# PP-Rev2.net
KiCad netlist of a schematic drawn in EAGLE
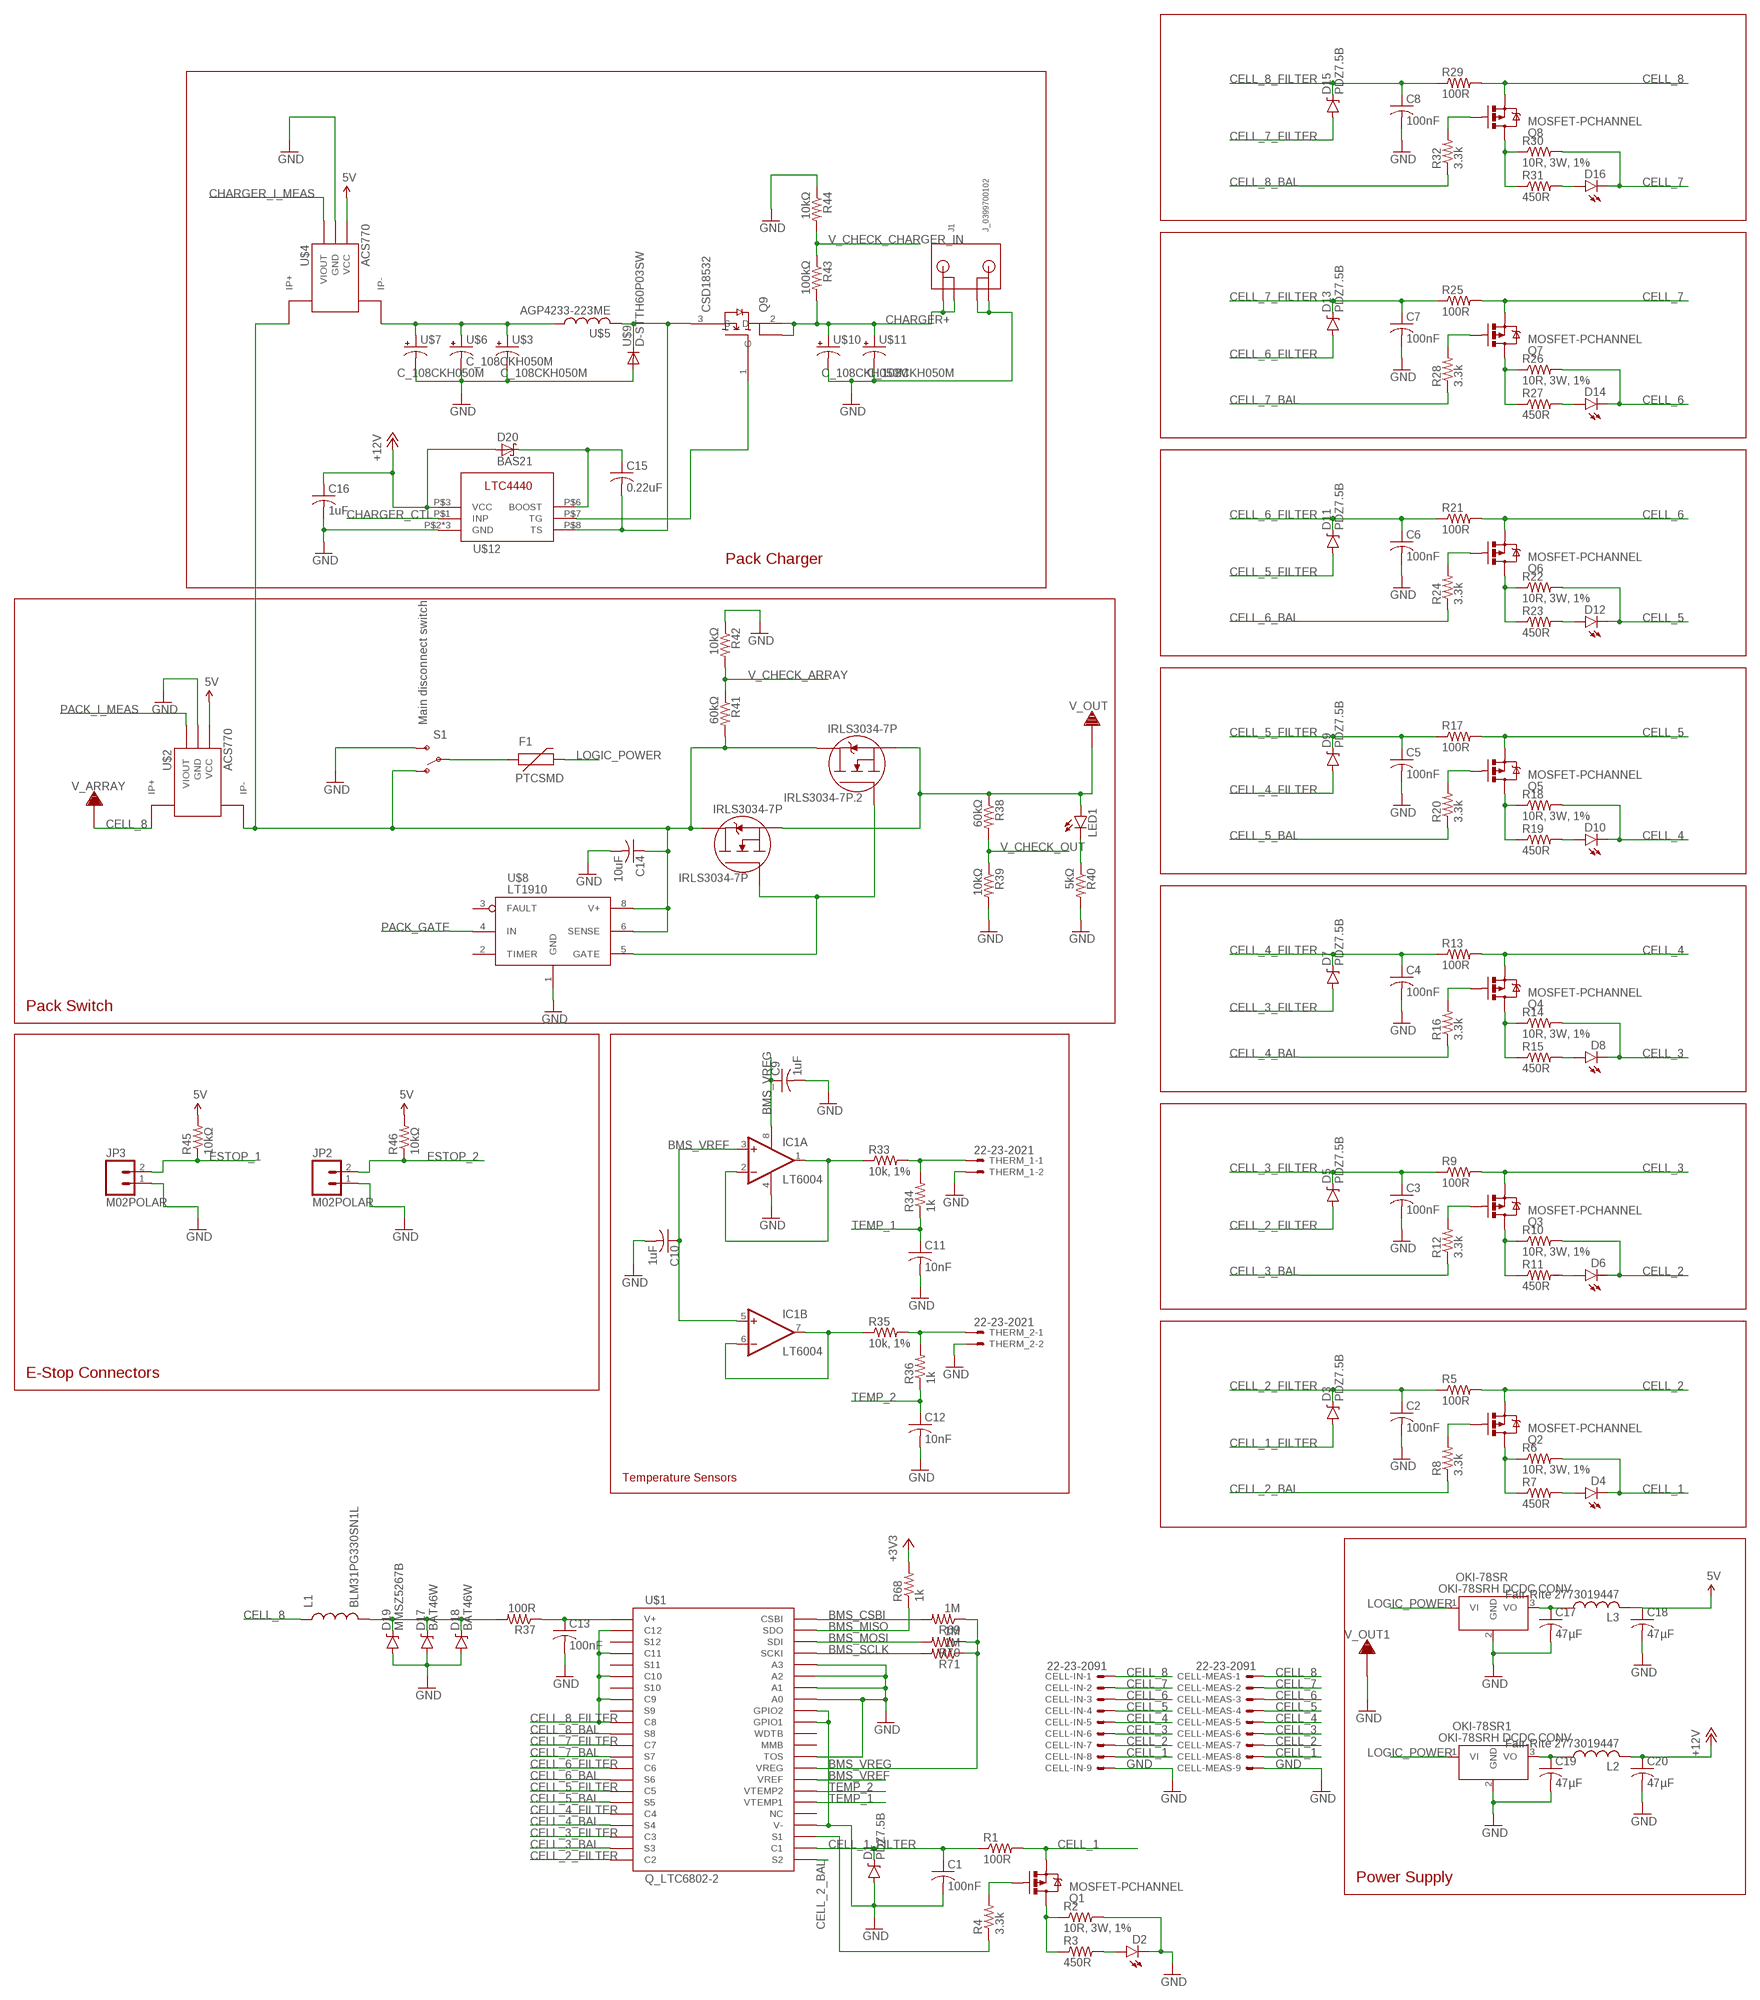
[diagram p0: schematic, sheet 1, part 1 of 2]
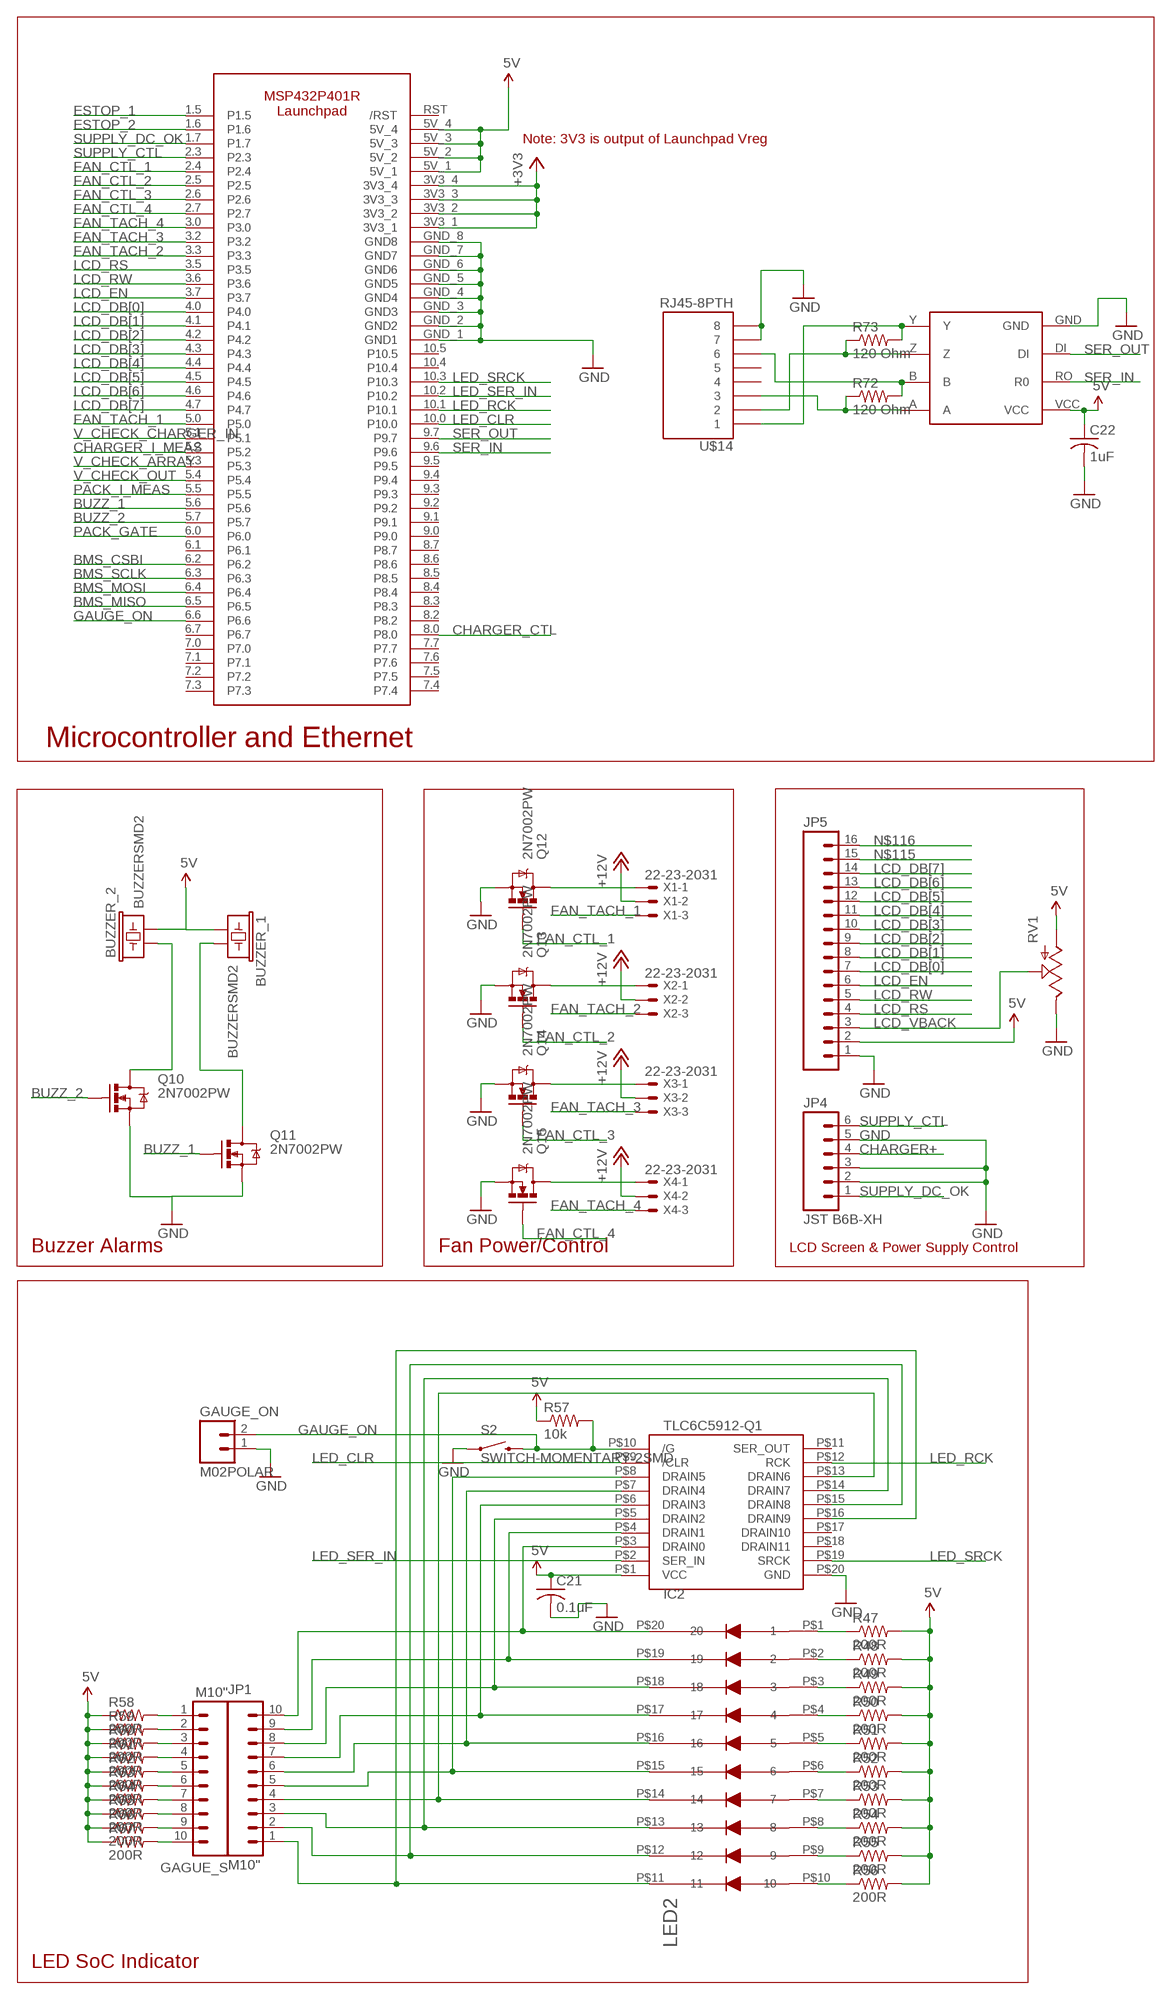
[diagram p1: schematic, sheet 1, part 2 of 2]

(export (version "E")
  (design (tool "Eeschema 10.0.6"))
  (components
    (comp (ref "BUZZER_1")
      (value "BUZZERSMD2")
      (footprint "eagle-import:BUZZER-CCV")
      (libsource (lib "eagle-import") (part "BUZZERSMD2"))
    )
    (comp (ref "BUZZER_2")
      (value "BUZZERSMD2")
      (footprint "eagle-import:BUZZER-CCV")
      (libsource (lib "eagle-import") (part "BUZZERSMD2"))
    )
    (comp (ref "C1")
      (value "100nF")
      (footprint "eagle-import:C1206")
      (libsource (lib "eagle-import") (part "C-USC1206"))
    )
    (comp (ref "C2")
      (value "100nF")
      (footprint "eagle-import:C1206")
      (libsource (lib "eagle-import") (part "C-USC1206"))
    )
    (comp (ref "C3")
      (value "100nF")
      (footprint "eagle-import:C1206")
      (libsource (lib "eagle-import") (part "C-USC1206"))
    )
    (comp (ref "C4")
      (value "100nF")
      (footprint "eagle-import:C1206")
      (libsource (lib "eagle-import") (part "C-USC1206"))
    )
    (comp (ref "C5")
      (value "100nF")
      (footprint "eagle-import:C1206")
      (libsource (lib "eagle-import") (part "C-USC1206"))
    )
    (comp (ref "C6")
      (value "100nF")
      (footprint "eagle-import:C1206")
      (libsource (lib "eagle-import") (part "C-USC1206"))
    )
    (comp (ref "C7")
      (value "100nF")
      (footprint "eagle-import:C1206")
      (libsource (lib "eagle-import") (part "C-USC1206"))
    )
    (comp (ref "C8")
      (value "100nF")
      (footprint "eagle-import:C1206")
      (libsource (lib "eagle-import") (part "C-USC1206"))
    )
    (comp (ref "C9")
      (value "1uF")
      (footprint "eagle-import:C1206")
      (libsource (lib "eagle-import") (part "C-USC1206"))
    )
    (comp (ref "C10")
      (value "1uF")
      (footprint "eagle-import:C1206")
      (libsource (lib "eagle-import") (part "C-USC1206"))
    )
    (comp (ref "C11")
      (value "10nF")
      (footprint "eagle-import:C1206")
      (libsource (lib "eagle-import") (part "C-USC1206"))
    )
    (comp (ref "C12")
      (value "10nF")
      (footprint "eagle-import:C1206")
      (libsource (lib "eagle-import") (part "C-USC1206"))
    )
    (comp (ref "C13")
      (value "100nF")
      (footprint "eagle-import:C1206")
      (libsource (lib "eagle-import") (part "C-USC1206"))
    )
    (comp (ref "C14")
      (value "10uF")
      (footprint "eagle-import:C1206")
      (libsource (lib "eagle-import") (part "C-USC1206"))
    )
    (comp (ref "C15")
      (value "0.22uF")
      (footprint "eagle-import:C1206")
      (libsource (lib "eagle-import") (part "C-USC1206"))
    )
    (comp (ref "C16")
      (value "1uF")
      (footprint "eagle-import:C1206")
      (libsource (lib "eagle-import") (part "C-USC1206"))
    )
    (comp (ref "C17")
      (value "47µF")
      (footprint "eagle-import:C1206")
      (libsource (lib "eagle-import") (part "resistor_C-USC1206"))
    )
    (comp (ref "C18")
      (value "47µF")
      (footprint "eagle-import:C1206")
      (libsource (lib "eagle-import") (part "resistor_C-USC1206"))
    )
    (comp (ref "C19")
      (value "47µF")
      (footprint "eagle-import:C1206")
      (libsource (lib "eagle-import") (part "resistor_C-USC1206"))
    )
    (comp (ref "C20")
      (value "47µF")
      (footprint "eagle-import:C1206")
      (libsource (lib "eagle-import") (part "resistor_C-USC1206"))
    )
    (comp (ref "C21")
      (value "0.1uF")
      (footprint "eagle-import:C1206")
      (libsource (lib "eagle-import") (part "resistor_C-USC1206"))
    )
    (comp (ref "C22")
      (value "1uF")
      (footprint "eagle-import:C1206")
      (libsource (lib "eagle-import") (part "resistor_C-USC1206"))
    )
    (comp (ref "CELL-IN")
      (value "22-23-2091")
      (footprint "eagle-import:22-23-2091")
      (fields (field (name "MF") "MOLEX"))
      (libsource (lib "eagle-import") (part "22-23-2091"))
    )
    (comp (ref "CELL-MEAS")
      (value "22-23-2091")
      (footprint "eagle-import:22-23-2091")
      (fields (field (name "MF") "MOLEX"))
      (libsource (lib "eagle-import") (part "22-23-2091"))
    )
    (comp (ref "D1")
      (value "PDZ7.5B")
      (footprint "eagle-import:SOD-323")
      (libsource (lib "eagle-import") (part "DIODE-ZENER5.6V"))
    )
    (comp (ref "D2")
      (value "LED1206")
      (footprint "eagle-import:LED-1206")
      (libsource (lib "eagle-import") (part "LED1206"))
    )
    (comp (ref "D3")
      (value "PDZ7.5B")
      (footprint "eagle-import:SOD-323")
      (libsource (lib "eagle-import") (part "DIODE-ZENER5.6V"))
    )
    (comp (ref "D4")
      (value "LED1206")
      (footprint "eagle-import:LED-1206")
      (libsource (lib "eagle-import") (part "LED1206"))
    )
    (comp (ref "D5")
      (value "PDZ7.5B")
      (footprint "eagle-import:SOD-323")
      (libsource (lib "eagle-import") (part "DIODE-ZENER5.6V"))
    )
    (comp (ref "D6")
      (value "LED1206")
      (footprint "eagle-import:LED-1206")
      (libsource (lib "eagle-import") (part "LED1206"))
    )
    (comp (ref "D7")
      (value "PDZ7.5B")
      (footprint "eagle-import:SOD-323")
      (libsource (lib "eagle-import") (part "DIODE-ZENER5.6V"))
    )
    (comp (ref "D8")
      (value "LED1206")
      (footprint "eagle-import:LED-1206")
      (libsource (lib "eagle-import") (part "LED1206"))
    )
    (comp (ref "D9")
      (value "PDZ7.5B")
      (footprint "eagle-import:SOD-323")
      (libsource (lib "eagle-import") (part "DIODE-ZENER5.6V"))
    )
    (comp (ref "D10")
      (value "LED1206")
      (footprint "eagle-import:LED-1206")
      (libsource (lib "eagle-import") (part "LED1206"))
    )
    (comp (ref "D11")
      (value "PDZ7.5B")
      (footprint "eagle-import:SOD-323")
      (libsource (lib "eagle-import") (part "DIODE-ZENER5.6V"))
    )
    (comp (ref "D12")
      (value "LED1206")
      (footprint "eagle-import:LED-1206")
      (libsource (lib "eagle-import") (part "LED1206"))
    )
    (comp (ref "D13")
      (value "PDZ7.5B")
      (footprint "eagle-import:SOD-323")
      (libsource (lib "eagle-import") (part "DIODE-ZENER5.6V"))
    )
    (comp (ref "D14")
      (value "LED1206")
      (footprint "eagle-import:LED-1206")
      (libsource (lib "eagle-import") (part "LED1206"))
    )
    (comp (ref "D15")
      (value "PDZ7.5B")
      (footprint "eagle-import:SOD-323")
      (libsource (lib "eagle-import") (part "DIODE-ZENER5.6V"))
    )
    (comp (ref "D16")
      (value "LED1206")
      (footprint "eagle-import:LED-1206")
      (libsource (lib "eagle-import") (part "LED1206"))
    )
    (comp (ref "D17")
      (value "BAT46W")
      (footprint "eagle-import:SOD-123")
      (libsource (lib "eagle-import") (part "DIODE-ZENER16V"))
    )
    (comp (ref "D18")
      (value "BAT46W")
      (footprint "eagle-import:SOD-123")
      (libsource (lib "eagle-import") (part "DIODE-ZENER16V"))
    )
    (comp (ref "D19")
      (value "MMSZ5267B")
      (footprint "eagle-import:SOD-123")
      (libsource (lib "eagle-import") (part "DIODE-ZENER16V"))
    )
    (comp (ref "D20")
      (value "BAS21")
      (footprint "eagle-import:SOT23")
      (libsource (lib "eagle-import") (part "BAS40"))
    )
    (comp (ref "F1")
      (value "PTCSMD")
      (footprint "eagle-import:PTC-1206")
      (libsource (lib "eagle-import") (part "PTCSMD"))
    )
    (comp (ref "GAGUE_S")
      (value "M10\"")
      (footprint "eagle-import:1X10")
      (libsource (lib "eagle-import") (part "M10{dblquote}"))
    )
    (comp (ref "GAUGE_ON")
      (value "M02POLAR")
      (footprint "eagle-import:MOLEX-1X2")
      (libsource (lib "eagle-import") (part "M02POLAR"))
    )
    (comp (ref "IC1")
      (value "LT6004")
      (footprint "eagle-import:MSOP08")
      (libsource (lib "eagle-import") (part "OPA2E345"))
    )
    (comp (ref "IC2")
      (value "TLC6C5912-Q1")
      (footprint "eagle-import:SOIC-20")
      (libsource (lib "eagle-import") (part "TLC6C5912-Q1"))
    )
    (comp (ref "IRLS3034-7P")
      (value "IRLS3034-7P")
      (footprint "eagle-import:D2PAK-7")
      (libsource (lib "eagle-import") (part "IRLS3034-7P"))
    )
    (comp (ref "IRLS3034-7P.2")
      (value "IRLS3034-7P")
      (footprint "eagle-import:D2PAK-7")
      (libsource (lib "eagle-import") (part "IRLS3034-7P"))
    )
    (comp (ref "J1")
      (value "J_0399700102")
      (footprint "eagle-import:J_2CONHC")
      (libsource (lib "eagle-import") (part "J_0399700102"))
    )
    (comp (ref "JP1")
      (value "M10\"")
      (footprint "eagle-import:1X10")
      (libsource (lib "eagle-import") (part "M10{dblquote}"))
    )
    (comp (ref "JP2")
      (value "M02POLAR")
      (footprint "eagle-import:MOLEX-1X2")
      (libsource (lib "eagle-import") (part "M02POLAR"))
    )
    (comp (ref "JP3")
      (value "M02POLAR")
      (footprint "eagle-import:MOLEX-1X2")
      (libsource (lib "eagle-import") (part "M02POLAR"))
    )
    (comp (ref "JP4")
      (value "JST B6B-XH")
      (footprint "eagle-import:MOLEX-1X6")
      (libsource (lib "eagle-import") (part "M06POLAR"))
    )
    (comp (ref "JP5")
      (value "M16LONGPADS")
      (footprint "eagle-import:1X16_LONGPADS")
      (libsource (lib "eagle-import") (part "M16LONGPADS"))
    )
    (comp (ref "L1")
      (value "BLM31PG330SN1L")
      (footprint "eagle-import:1210")
      (libsource (lib "eagle-import") (part "INDUCTOR1210"))
    )
    (comp (ref "L2")
      (value "Fair-Rite 2773019447")
      (footprint "eagle-import:L8530M")
      (libsource (lib "eagle-import") (part "L-USL8530M"))
    )
    (comp (ref "L3")
      (value "Fair-Rite 2773019447")
      (footprint "eagle-import:L8530M")
      (libsource (lib "eagle-import") (part "L-USL8530M"))
    )
    (comp (ref "LED1")
      (value "LED1206")
      (footprint "eagle-import:LED-1206")
      (libsource (lib "eagle-import") (part "LED1206"))
    )
    (comp (ref "LED2")
      (value "LED-DC7G3HWA")
      (footprint "eagle-import:LED-10")
      (libsource (lib "eagle-import") (part "LED-DC7G3HWA"))
    )
    (comp (ref "OKI-78SR")
      (value "Q_OKI-78SR5")
      (footprint "eagle-import:OKI-78SRH")
      (libsource (lib "eagle-import") (part "Q_OKI-78SR"))
    )
    (comp (ref "OKI-78SR1")
      (value "Q_OKI-78SR12")
      (footprint "eagle-import:OKI-78SRH")
      (libsource (lib "eagle-import") (part "Q_OKI-78SR"))
    )
    (comp (ref "Q1")
      (value "MOSFET-PCHANNEL")
      (footprint "eagle-import:SOT23-3")
      (libsource (lib "eagle-import") (part "MOSFET-PCHANNEL"))
    )
    (comp (ref "Q2")
      (value "MOSFET-PCHANNEL")
      (footprint "eagle-import:SOT23-3")
      (libsource (lib "eagle-import") (part "MOSFET-PCHANNEL"))
    )
    (comp (ref "Q3")
      (value "MOSFET-PCHANNEL")
      (footprint "eagle-import:SOT23-3")
      (libsource (lib "eagle-import") (part "MOSFET-PCHANNEL"))
    )
    (comp (ref "Q4")
      (value "MOSFET-PCHANNEL")
      (footprint "eagle-import:SOT23-3")
      (libsource (lib "eagle-import") (part "MOSFET-PCHANNEL"))
    )
    (comp (ref "Q5")
      (value "MOSFET-PCHANNEL")
      (footprint "eagle-import:SOT23-3")
      (libsource (lib "eagle-import") (part "MOSFET-PCHANNEL"))
    )
    (comp (ref "Q6")
      (value "MOSFET-PCHANNEL")
      (footprint "eagle-import:SOT23-3")
      (libsource (lib "eagle-import") (part "MOSFET-PCHANNEL"))
    )
    (comp (ref "Q7")
      (value "MOSFET-PCHANNEL")
      (footprint "eagle-import:SOT23-3")
      (libsource (lib "eagle-import") (part "MOSFET-PCHANNEL"))
    )
    (comp (ref "Q8")
      (value "MOSFET-PCHANNEL")
      (footprint "eagle-import:SOT23-3")
      (libsource (lib "eagle-import") (part "MOSFET-PCHANNEL"))
    )
    (comp (ref "Q9")
      (value "CSD18532")
      (footprint "eagle-import:TO-220-FLAT")
      (libsource (lib "eagle-import") (part "Q_CSD18532KCSPCB"))
    )
    (comp (ref "Q10")
      (value "2N7002PW")
      (footprint "eagle-import:SOT323")
      (libsource (lib "eagle-import") (part "MOSFET-NCHANNEL2N7002PW"))
    )
    (comp (ref "Q11")
      (value "2N7002PW")
      (footprint "eagle-import:SOT323")
      (libsource (lib "eagle-import") (part "MOSFET-NCHANNEL2N7002PW"))
    )
    (comp (ref "Q12")
      (value "2N7002PW")
      (footprint "eagle-import:SOT323")
      (libsource (lib "eagle-import") (part "MOSFET-NCHANNEL2N7002PW"))
    )
    (comp (ref "Q13")
      (value "2N7002PW")
      (footprint "eagle-import:SOT323")
      (libsource (lib "eagle-import") (part "MOSFET-NCHANNEL2N7002PW"))
    )
    (comp (ref "Q14")
      (value "2N7002PW")
      (footprint "eagle-import:SOT323")
      (libsource (lib "eagle-import") (part "MOSFET-NCHANNEL2N7002PW"))
    )
    (comp (ref "Q15")
      (value "2N7002PW")
      (footprint "eagle-import:SOT323")
      (libsource (lib "eagle-import") (part "MOSFET-NCHANNEL2N7002PW"))
    )
    (comp (ref "R1")
      (value "100R")
      (footprint "eagle-import:R1206")
      (libsource (lib "eagle-import") (part "R-US_R1206"))
    )
    (comp (ref "R2")
      (value "10R, 3W, 1%")
      (footprint "eagle-import:AXIAL-0.6")
      (libsource (lib "eagle-import") (part "SparkFun-Resistors_RESISTORPTH-1W"))
    )
    (comp (ref "R3")
      (value "450R")
      (footprint "eagle-import:1206")
      (libsource (lib "eagle-import") (part "SparkFun-Resistors_RESISTOR1206"))
    )
    (comp (ref "R4")
      (value "3.3k")
      (footprint "eagle-import:1206")
      (libsource (lib "eagle-import") (part "SparkFun-Resistors_RESISTOR1206"))
    )
    (comp (ref "R5")
      (value "100R")
      (footprint "eagle-import:R1206")
      (libsource (lib "eagle-import") (part "R-US_R1206"))
    )
    (comp (ref "R6")
      (value "10R, 3W, 1%")
      (footprint "eagle-import:AXIAL-0.6")
      (libsource (lib "eagle-import") (part "SparkFun-Resistors_RESISTORPTH-1W"))
    )
    (comp (ref "R7")
      (value "450R")
      (footprint "eagle-import:1206")
      (libsource (lib "eagle-import") (part "SparkFun-Resistors_RESISTOR1206"))
    )
    (comp (ref "R8")
      (value "3.3k")
      (footprint "eagle-import:1206")
      (libsource (lib "eagle-import") (part "SparkFun-Resistors_RESISTOR1206"))
    )
    (comp (ref "R9")
      (value "100R")
      (footprint "eagle-import:R1206")
      (libsource (lib "eagle-import") (part "R-US_R1206"))
    )
    (comp (ref "R10")
      (value "10R, 3W, 1%")
      (footprint "eagle-import:AXIAL-0.6")
      (libsource (lib "eagle-import") (part "SparkFun-Resistors_RESISTORPTH-1W"))
    )
    (comp (ref "R11")
      (value "450R")
      (footprint "eagle-import:1206")
      (libsource (lib "eagle-import") (part "SparkFun-Resistors_RESISTOR1206"))
    )
    (comp (ref "R12")
      (value "3.3k")
      (footprint "eagle-import:1206")
      (libsource (lib "eagle-import") (part "SparkFun-Resistors_RESISTOR1206"))
    )
    (comp (ref "R13")
      (value "100R")
      (footprint "eagle-import:R1206")
      (libsource (lib "eagle-import") (part "R-US_R1206"))
    )
    (comp (ref "R14")
      (value "10R, 3W, 1%")
      (footprint "eagle-import:AXIAL-0.6")
      (libsource (lib "eagle-import") (part "SparkFun-Resistors_RESISTORPTH-1W"))
    )
    (comp (ref "R15")
      (value "450R")
      (footprint "eagle-import:1206")
      (libsource (lib "eagle-import") (part "SparkFun-Resistors_RESISTOR1206"))
    )
    (comp (ref "R16")
      (value "3.3k")
      (footprint "eagle-import:1206")
      (libsource (lib "eagle-import") (part "SparkFun-Resistors_RESISTOR1206"))
    )
    (comp (ref "R17")
      (value "100R")
      (footprint "eagle-import:R1206")
      (libsource (lib "eagle-import") (part "R-US_R1206"))
    )
    (comp (ref "R18")
      (value "10R, 3W, 1%")
      (footprint "eagle-import:AXIAL-0.6")
      (libsource (lib "eagle-import") (part "SparkFun-Resistors_RESISTORPTH-1W"))
    )
    (comp (ref "R19")
      (value "450R")
      (footprint "eagle-import:1206")
      (libsource (lib "eagle-import") (part "SparkFun-Resistors_RESISTOR1206"))
    )
    (comp (ref "R20")
      (value "3.3k")
      (footprint "eagle-import:1206")
      (libsource (lib "eagle-import") (part "SparkFun-Resistors_RESISTOR1206"))
    )
    (comp (ref "R21")
      (value "100R")
      (footprint "eagle-import:R1206")
      (libsource (lib "eagle-import") (part "R-US_R1206"))
    )
    (comp (ref "R22")
      (value "10R, 3W, 1%")
      (footprint "eagle-import:AXIAL-0.6")
      (libsource (lib "eagle-import") (part "SparkFun-Resistors_RESISTORPTH-1W"))
    )
    (comp (ref "R23")
      (value "450R")
      (footprint "eagle-import:1206")
      (libsource (lib "eagle-import") (part "SparkFun-Resistors_RESISTOR1206"))
    )
    (comp (ref "R24")
      (value "3.3k")
      (footprint "eagle-import:1206")
      (libsource (lib "eagle-import") (part "SparkFun-Resistors_RESISTOR1206"))
    )
    (comp (ref "R25")
      (value "100R")
      (footprint "eagle-import:R1206")
      (libsource (lib "eagle-import") (part "R-US_R1206"))
    )
    (comp (ref "R26")
      (value "10R, 3W, 1%")
      (footprint "eagle-import:AXIAL-0.6")
      (libsource (lib "eagle-import") (part "SparkFun-Resistors_RESISTORPTH-1W"))
    )
    (comp (ref "R27")
      (value "450R")
      (footprint "eagle-import:1206")
      (libsource (lib "eagle-import") (part "SparkFun-Resistors_RESISTOR1206"))
    )
    (comp (ref "R28")
      (value "3.3k")
      (footprint "eagle-import:1206")
      (libsource (lib "eagle-import") (part "SparkFun-Resistors_RESISTOR1206"))
    )
    (comp (ref "R29")
      (value "100R")
      (footprint "eagle-import:R1206")
      (libsource (lib "eagle-import") (part "R-US_R1206"))
    )
    (comp (ref "R30")
      (value "10R, 3W, 1%")
      (footprint "eagle-import:AXIAL-0.6")
      (libsource (lib "eagle-import") (part "SparkFun-Resistors_RESISTORPTH-1W"))
    )
    (comp (ref "R31")
      (value "450R")
      (footprint "eagle-import:1206")
      (libsource (lib "eagle-import") (part "SparkFun-Resistors_RESISTOR1206"))
    )
    (comp (ref "R32")
      (value "3.3k")
      (footprint "eagle-import:1206")
      (libsource (lib "eagle-import") (part "SparkFun-Resistors_RESISTOR1206"))
    )
    (comp (ref "R33")
      (value "10k, 1%")
      (footprint "eagle-import:R1206")
      (libsource (lib "eagle-import") (part "R-US_R1206"))
    )
    (comp (ref "R34")
      (value "1k")
      (footprint "eagle-import:R1206")
      (libsource (lib "eagle-import") (part "R-US_R1206"))
    )
    (comp (ref "R35")
      (value "10k, 1%")
      (footprint "eagle-import:R1206")
      (libsource (lib "eagle-import") (part "R-US_R1206"))
    )
    (comp (ref "R36")
      (value "1k")
      (footprint "eagle-import:R1206")
      (libsource (lib "eagle-import") (part "R-US_R1206"))
    )
    (comp (ref "R37")
      (value "100R")
      (footprint "eagle-import:R1206")
      (libsource (lib "eagle-import") (part "R-US_R1206"))
    )
    (comp (ref "R38")
      (value "60kΩ")
      (footprint "eagle-import:R1206")
      (libsource (lib "eagle-import") (part "resistor_R-US_R1206"))
    )
    (comp (ref "R39")
      (value "10kΩ")
      (footprint "eagle-import:R1206")
      (libsource (lib "eagle-import") (part "resistor_R-US_R1206"))
    )
    (comp (ref "R40")
      (value "5kΩ")
      (footprint "eagle-import:R1206")
      (libsource (lib "eagle-import") (part "resistor_R-US_R1206"))
    )
    (comp (ref "R41")
      (value "60kΩ")
      (footprint "eagle-import:R1206")
      (libsource (lib "eagle-import") (part "resistor_R-US_R1206"))
    )
    (comp (ref "R42")
      (value "10kΩ")
      (footprint "eagle-import:R1206")
      (libsource (lib "eagle-import") (part "resistor_R-US_R1206"))
    )
    (comp (ref "R43")
      (value "100kΩ")
      (footprint "eagle-import:R1206")
      (libsource (lib "eagle-import") (part "resistor_R-US_R1206"))
    )
    (comp (ref "R44")
      (value "10kΩ")
      (footprint "eagle-import:R1206")
      (libsource (lib "eagle-import") (part "resistor_R-US_R1206"))
    )
    (comp (ref "R45")
      (value "10kΩ")
      (footprint "eagle-import:R1206")
      (libsource (lib "eagle-import") (part "resistor_R-US_R1206"))
    )
    (comp (ref "R46")
      (value "10kΩ")
      (footprint "eagle-import:R1206")
      (libsource (lib "eagle-import") (part "resistor_R-US_R1206"))
    )
    (comp (ref "R47")
      (value "200R")
      (footprint "eagle-import:R1206")
      (libsource (lib "eagle-import") (part "R-US_R1206"))
    )
    (comp (ref "R48")
      (value "200R")
      (footprint "eagle-import:R1206")
      (libsource (lib "eagle-import") (part "R-US_R1206"))
    )
    (comp (ref "R49")
      (value "200R")
      (footprint "eagle-import:R1206")
      (libsource (lib "eagle-import") (part "R-US_R1206"))
    )
    (comp (ref "R50")
      (value "200R")
      (footprint "eagle-import:R1206")
      (libsource (lib "eagle-import") (part "R-US_R1206"))
    )
    (comp (ref "R51")
      (value "200R")
      (footprint "eagle-import:R1206")
      (libsource (lib "eagle-import") (part "R-US_R1206"))
    )
    (comp (ref "R52")
      (value "200R")
      (footprint "eagle-import:R1206")
      (libsource (lib "eagle-import") (part "R-US_R1206"))
    )
    (comp (ref "R53")
      (value "200R")
      (footprint "eagle-import:R1206")
      (libsource (lib "eagle-import") (part "R-US_R1206"))
    )
    (comp (ref "R54")
      (value "200R")
      (footprint "eagle-import:R1206")
      (libsource (lib "eagle-import") (part "R-US_R1206"))
    )
    (comp (ref "R55")
      (value "200R")
      (footprint "eagle-import:R1206")
      (libsource (lib "eagle-import") (part "R-US_R1206"))
    )
    (comp (ref "R56")
      (value "200R")
      (footprint "eagle-import:R1206")
      (libsource (lib "eagle-import") (part "R-US_R1206"))
    )
    (comp (ref "R57")
      (value "10k")
      (footprint "eagle-import:R1206")
      (libsource (lib "eagle-import") (part "R-US_R1206"))
    )
    (comp (ref "R58")
      (value "200R")
      (footprint "eagle-import:R1206")
      (libsource (lib "eagle-import") (part "R-US_R1206"))
    )
    (comp (ref "R59")
      (value "200R")
      (footprint "eagle-import:R1206")
      (libsource (lib "eagle-import") (part "R-US_R1206"))
    )
    (comp (ref "R60")
      (value "200R")
      (footprint "eagle-import:R1206")
      (libsource (lib "eagle-import") (part "R-US_R1206"))
    )
    (comp (ref "R61")
      (value "200R")
      (footprint "eagle-import:R1206")
      (libsource (lib "eagle-import") (part "R-US_R1206"))
    )
    (comp (ref "R62")
      (value "200R")
      (footprint "eagle-import:R1206")
      (libsource (lib "eagle-import") (part "R-US_R1206"))
    )
    (comp (ref "R63")
      (value "200R")
      (footprint "eagle-import:R1206")
      (libsource (lib "eagle-import") (part "R-US_R1206"))
    )
    (comp (ref "R64")
      (value "200R")
      (footprint "eagle-import:R1206")
      (libsource (lib "eagle-import") (part "R-US_R1206"))
    )
    (comp (ref "R65")
      (value "200R")
      (footprint "eagle-import:R1206")
      (libsource (lib "eagle-import") (part "R-US_R1206"))
    )
    (comp (ref "R66")
      (value "200R")
      (footprint "eagle-import:R1206")
      (libsource (lib "eagle-import") (part "R-US_R1206"))
    )
    (comp (ref "R67")
      (value "200R")
      (footprint "eagle-import:R1206")
      (libsource (lib "eagle-import") (part "R-US_R1206"))
    )
    (comp (ref "R68")
      (value "1k")
      (footprint "eagle-import:R1206")
      (libsource (lib "eagle-import") (part "R-US_R1206"))
    )
    (comp (ref "R69")
      (value "1M")
      (footprint "eagle-import:R1206")
      (libsource (lib "eagle-import") (part "R-US_R1206"))
    )
    (comp (ref "R70")
      (value "1M")
      (footprint "eagle-import:R1206")
      (libsource (lib "eagle-import") (part "R-US_R1206"))
    )
    (comp (ref "R71")
      (value "1M")
      (footprint "eagle-import:R1206")
      (libsource (lib "eagle-import") (part "R-US_R1206"))
    )
    (comp (ref "R72")
      (value "120 Ohm")
      (footprint "eagle-import:1206")
      (libsource (lib "eagle-import") (part "RESISTOR1206"))
    )
    (comp (ref "R73")
      (value "120 Ohm")
      (footprint "eagle-import:1206")
      (libsource (lib "eagle-import") (part "RESISTOR1206"))
    )
    (comp (ref "RV1")
      (value "POTTRIM")
      (footprint "eagle-import:TRIM_POT")
      (libsource (lib "eagle-import") (part "POTTRIM"))
    )
    (comp (ref "S1")
      (value "SWITCH-SPDTPTH")
      (footprint "eagle-import:SWITCH-SPDT")
      (libsource (lib "eagle-import") (part "SWITCH-SPDTPTH"))
    )
    (comp (ref "S2")
      (value "SWITCH-MOMENTARY-2SMD")
      (footprint "eagle-import:TACTILE-SWITCH-SMD")
      (libsource (lib "eagle-import") (part "SWITCH-MOMENTARY-2SMD"))
    )
    (comp (ref "THERM_1")
      (value "22-23-2021")
      (footprint "eagle-import:22-23-2021")
      (fields (field (name "MF") "MOLEX"))
      (libsource (lib "eagle-import") (part "22-23-2021"))
    )
    (comp (ref "THERM_2")
      (value "22-23-2021")
      (footprint "eagle-import:22-23-2021")
      (fields (field (name "MF") "MOLEX"))
      (libsource (lib "eagle-import") (part "22-23-2021"))
    )
    (comp (ref "U$1")
      (value "Q_LTC6802-2")
      (footprint "eagle-import:SSOP44")
      (libsource (lib "eagle-import") (part "Q_LTC6802-2"))
    )
    (comp (ref "U$2")
      (value "ACS770")
      (footprint "eagle-import:PFF_LEADFORM")
      (libsource (lib "eagle-import") (part "ACS770"))
    )
    (comp (ref "U$3")
      (value "C_108CKH050M")
      (footprint "eagle-import:C_16MM")
      (libsource (lib "eagle-import") (part "C_108CKH050M"))
    )
    (comp (ref "U$4")
      (value "ACS770")
      (footprint "eagle-import:PFF_LEADFORM")
      (libsource (lib "eagle-import") (part "ACS770"))
    )
    (comp (ref "U$5")
      (value "AGP4233-223ME")
      (footprint "eagle-import:AGP4233")
      (libsource (lib "eagle-import") (part "AGP4233"))
    )
    (comp (ref "U$6")
      (value "C_108CKH050M")
      (footprint "eagle-import:C_16MM")
      (libsource (lib "eagle-import") (part "C_108CKH050M"))
    )
    (comp (ref "U$7")
      (value "C_108CKH050M")
      (footprint "eagle-import:C_16MM")
      (libsource (lib "eagle-import") (part "C_108CKH050M"))
    )
    (comp (ref "U$8")
      (value "LT1910")
      (footprint "eagle-import:SO8")
      (libsource (lib "eagle-import") (part "LT1910"))
    )
    (comp (ref "U$9")
      (value "D-STTH60P03SW")
      (footprint "eagle-import:TO-247-VERT")
      (libsource (lib "eagle-import") (part "D-STTH60P03SW"))
    )
    (comp (ref "U$10")
      (value "C_108CKH050M")
      (footprint "eagle-import:C_16MM")
      (libsource (lib "eagle-import") (part "C_108CKH050M"))
    )
    (comp (ref "U$11")
      (value "C_108CKH050M")
      (footprint "eagle-import:C_16MM")
      (libsource (lib "eagle-import") (part "C_108CKH050M"))
    )
    (comp (ref "U$12")
      (value "LTC4440")
      (footprint "eagle-import:MS8E")
      (libsource (lib "eagle-import") (part "LTC4440"))
    )
    (comp (ref "U$13")
      (value "MSP432P401R-LAUNCHPAD")
      (footprint "eagle-import:MSP432P401R-LAUNCHPAD")
      (libsource (lib "eagle-import") (part "MSP432P401R-LAUNCHPAD"))
    )
    (comp (ref "U$14")
      (value "RJ45-8PTH")
      (footprint "eagle-import:RJ45-8")
      (libsource (lib "eagle-import") (part "RJ45-8PTH"))
    )
    (comp (ref "U$15")
      (value "MAX3077")
      (footprint "eagle-import:MAX3070E")
      (libsource (lib "eagle-import") (part "MAX3077"))
    )
    (comp (ref "V_ARRAY")
      (value "TERMINAL_HOLE")
      (footprint "eagle-import:LARGE_TERMINAL_HOLE")
      (libsource (lib "eagle-import") (part "TERMINAL_HOLE"))
    )
    (comp (ref "V_OUT")
      (value "TERMINAL_HOLE")
      (footprint "eagle-import:LARGE_TERMINAL_HOLE")
      (libsource (lib "eagle-import") (part "TERMINAL_HOLE"))
    )
    (comp (ref "V_OUT1")
      (value "TERMINAL_HOLE")
      (footprint "eagle-import:LARGE_TERMINAL_HOLE")
      (libsource (lib "eagle-import") (part "TERMINAL_HOLE"))
    )
    (comp (ref "X1")
      (value "22-23-2031")
      (footprint "eagle-import:22-23-2031")
      (fields (field (name "MF") "MOLEX"))
      (libsource (lib "eagle-import") (part "22-23-2031"))
    )
    (comp (ref "X2")
      (value "22-23-2031")
      (footprint "eagle-import:22-23-2031")
      (fields (field (name "MF") "MOLEX"))
      (libsource (lib "eagle-import") (part "22-23-2031"))
    )
    (comp (ref "X3")
      (value "22-23-2031")
      (footprint "eagle-import:22-23-2031")
      (fields (field (name "MF") "MOLEX"))
      (libsource (lib "eagle-import") (part "22-23-2031"))
    )
    (comp (ref "X4")
      (value "22-23-2031")
      (footprint "eagle-import:22-23-2031")
      (fields (field (name "MF") "MOLEX"))
      (libsource (lib "eagle-import") (part "22-23-2031"))
    )
  )
  (nets
    (net (code "1") (name "+3V3") (class "Default")
      (node (ref "R68") (pin "2") (pinfunction "2_2") (pintype "passive"))
      (node (ref "U$13") (pin "3V3_1") (pinfunction "3V3_1_3V3_1") (pintype "bidirectional"))
      (node (ref "U$13") (pin "3V3_2") (pinfunction "3V3_2_3V3_2") (pintype "bidirectional"))
      (node (ref "U$13") (pin "3V3_3") (pinfunction "3V3_3_3V3_3") (pintype "bidirectional"))
      (node (ref "U$13") (pin "3V3_4") (pinfunction "3V3_4_3V3_4") (pintype "bidirectional"))
    )
    (net (code "2") (name "+12V") (class "Default")
      (node (ref "C16") (pin "1") (pinfunction "1_1") (pintype "passive"))
      (node (ref "C20") (pin "1") (pinfunction "1_1") (pintype "passive"))
      (node (ref "D20") (pin "1") (pinfunction "A_1") (pintype "passive"))
      (node (ref "L2") (pin "2") (pinfunction "2_2") (pintype "passive"))
      (node (ref "U$12") (pin "P$3") (pinfunction "VCC_P$3") (pintype "bidirectional"))
      (node (ref "X1") (pin "2") (pinfunction "S_2") (pintype "passive"))
      (node (ref "X2") (pin "2") (pinfunction "S_2") (pintype "passive"))
      (node (ref "X3") (pin "2") (pinfunction "S_2") (pintype "passive"))
      (node (ref "X4") (pin "2") (pinfunction "S_2") (pintype "passive"))
    )
    (net (code "3") (name "/BMS_CSBI") (class "Default")
      (node (ref "R69") (pin "2") (pinfunction "2_2") (pintype "passive"))
      (node (ref "U$1") (pin "44") (pinfunction "CSBI_44") (pintype "bidirectional"))
      (node (ref "U$13") (pin "6.2") (pinfunction "P6.2_6.2") (pintype "bidirectional"))
    )
    (net (code "4") (name "/BMS_MISO") (class "Default")
      (node (ref "R68") (pin "1") (pinfunction "1_1") (pintype "passive"))
      (node (ref "U$1") (pin "43") (pinfunction "SDO_43") (pintype "bidirectional"))
      (node (ref "U$13") (pin "6.5") (pinfunction "P6.5_6.5") (pintype "bidirectional"))
    )
    (net (code "5") (name "/BMS_MOSI") (class "Default")
      (node (ref "R70") (pin "2") (pinfunction "2_2") (pintype "passive"))
      (node (ref "U$1") (pin "42") (pinfunction "SDI_42") (pintype "bidirectional"))
      (node (ref "U$13") (pin "6.4") (pinfunction "P6.4_6.4") (pintype "bidirectional"))
    )
    (net (code "6") (name "/BMS_SCLK") (class "Default")
      (node (ref "R71") (pin "2") (pinfunction "2_2") (pintype "passive"))
      (node (ref "U$1") (pin "41") (pinfunction "SCKI_41") (pintype "bidirectional"))
      (node (ref "U$13") (pin "6.3") (pinfunction "P6.3_6.3") (pintype "bidirectional"))
    )
    (net (code "7") (name "/BMS_VREF") (class "Default")
      (node (ref "C10") (pin "1") (pinfunction "1_1") (pintype "passive"))
      (node (ref "IC1") (pin "3") (pinfunction "+IN_3") (pintype "input"))
      (node (ref "IC1") (pin "5") (pinfunction "+IN_5") (pintype "input"))
      (node (ref "U$1") (pin "30") (pinfunction "VREF_30") (pintype "bidirectional"))
    )
    (net (code "8") (name "/BMS_VREG") (class "Default")
      (node (ref "C9") (pin "1") (pinfunction "1_1") (pintype "passive"))
      (node (ref "IC1") (pin "8") (pinfunction "V+_8") (pintype "power_in"))
      (node (ref "R69") (pin "1") (pinfunction "1_1") (pintype "passive"))
      (node (ref "R70") (pin "1") (pinfunction "1_1") (pintype "passive"))
      (node (ref "R71") (pin "1") (pinfunction "1_1") (pintype "passive"))
      (node (ref "U$1") (pin "31") (pinfunction "VREG_31") (pintype "bidirectional"))
    )
    (net (code "9") (name "/BUZZ_1") (class "Default")
      (node (ref "Q11") (pin "1") (pinfunction "G_1") (pintype "passive"))
      (node (ref "U$13") (pin "5.6") (pinfunction "P5.6_5.6") (pintype "bidirectional"))
    )
    (net (code "10") (name "/BUZZ_2") (class "Default")
      (node (ref "Q10") (pin "1") (pinfunction "G_1") (pintype "passive"))
      (node (ref "U$13") (pin "5.7") (pinfunction "P5.7_5.7") (pintype "bidirectional"))
    )
    (net (code "11") (name "/CELL_1") (class "Default")
      (node (ref "CELL-IN") (pin "8") (pinfunction "S_8") (pintype "passive"))
      (node (ref "CELL-MEAS") (pin "8") (pinfunction "S_8") (pintype "passive"))
      (node (ref "D4") (pin "C") (pinfunction "C_C") (pintype "passive"))
      (node (ref "Q1") (pin "2") (pinfunction "S_2") (pintype "passive"))
      (node (ref "R1") (pin "2") (pinfunction "2_2") (pintype "passive"))
      (node (ref "R6") (pin "P$2") (pinfunction "2_P$2") (pintype "passive"))
    )
    (net (code "12") (name "/CELL_1_FILTER") (class "Default")
      (node (ref "C1") (pin "1") (pinfunction "1_1") (pintype "passive"))
      (node (ref "D1") (pin "C") (pinfunction "C_C") (pintype "passive"))
      (node (ref "D3") (pin "A") (pinfunction "A_A") (pintype "passive"))
      (node (ref "R1") (pin "1") (pinfunction "1_1") (pintype "passive"))
      (node (ref "U$1") (pin "24") (pinfunction "C1_24") (pintype "bidirectional"))
    )
    (net (code "13") (name "/CELL_2") (class "Default")
      (node (ref "CELL-IN") (pin "7") (pinfunction "S_7") (pintype "passive"))
      (node (ref "CELL-MEAS") (pin "7") (pinfunction "S_7") (pintype "passive"))
      (node (ref "D6") (pin "C") (pinfunction "C_C") (pintype "passive"))
      (node (ref "Q2") (pin "2") (pinfunction "S_2") (pintype "passive"))
      (node (ref "R10") (pin "P$2") (pinfunction "2_P$2") (pintype "passive"))
      (node (ref "R5") (pin "2") (pinfunction "2_2") (pintype "passive"))
    )
    (net (code "14") (name "/CELL_2_BAL") (class "Default")
      (node (ref "R8") (pin "1") (pinfunction "1_1") (pintype "passive"))
      (node (ref "U$1") (pin "23") (pinfunction "S2_23") (pintype "bidirectional"))
    )
    (net (code "15") (name "/CELL_2_FILTER") (class "Default")
      (node (ref "C2") (pin "1") (pinfunction "1_1") (pintype "passive"))
      (node (ref "D3") (pin "C") (pinfunction "C_C") (pintype "passive"))
      (node (ref "D5") (pin "A") (pinfunction "A_A") (pintype "passive"))
      (node (ref "R5") (pin "1") (pinfunction "1_1") (pintype "passive"))
      (node (ref "U$1") (pin "22") (pinfunction "C2_22") (pintype "bidirectional"))
    )
    (net (code "16") (name "/CELL_3") (class "Default")
      (node (ref "CELL-IN") (pin "6") (pinfunction "S_6") (pintype "passive"))
      (node (ref "CELL-MEAS") (pin "6") (pinfunction "S_6") (pintype "passive"))
      (node (ref "D8") (pin "C") (pinfunction "C_C") (pintype "passive"))
      (node (ref "Q3") (pin "2") (pinfunction "S_2") (pintype "passive"))
      (node (ref "R14") (pin "P$2") (pinfunction "2_P$2") (pintype "passive"))
      (node (ref "R9") (pin "2") (pinfunction "2_2") (pintype "passive"))
    )
    (net (code "17") (name "/CELL_3_BAL") (class "Default")
      (node (ref "R12") (pin "1") (pinfunction "1_1") (pintype "passive"))
      (node (ref "U$1") (pin "21") (pinfunction "S3_21") (pintype "bidirectional"))
    )
    (net (code "18") (name "/CELL_3_FILTER") (class "Default")
      (node (ref "C3") (pin "1") (pinfunction "1_1") (pintype "passive"))
      (node (ref "D5") (pin "C") (pinfunction "C_C") (pintype "passive"))
      (node (ref "D7") (pin "A") (pinfunction "A_A") (pintype "passive"))
      (node (ref "R9") (pin "1") (pinfunction "1_1") (pintype "passive"))
      (node (ref "U$1") (pin "20") (pinfunction "C3_20") (pintype "bidirectional"))
    )
    (net (code "19") (name "/CELL_4") (class "Default")
      (node (ref "CELL-IN") (pin "5") (pinfunction "S_5") (pintype "passive"))
      (node (ref "CELL-MEAS") (pin "5") (pinfunction "S_5") (pintype "passive"))
      (node (ref "D10") (pin "C") (pinfunction "C_C") (pintype "passive"))
      (node (ref "Q4") (pin "2") (pinfunction "S_2") (pintype "passive"))
      (node (ref "R13") (pin "2") (pinfunction "2_2") (pintype "passive"))
      (node (ref "R18") (pin "P$2") (pinfunction "2_P$2") (pintype "passive"))
    )
    (net (code "20") (name "/CELL_4_BAL") (class "Default")
      (node (ref "R16") (pin "1") (pinfunction "1_1") (pintype "passive"))
      (node (ref "U$1") (pin "19") (pinfunction "S4_19") (pintype "bidirectional"))
    )
    (net (code "21") (name "/CELL_4_FILTER") (class "Default")
      (node (ref "C4") (pin "1") (pinfunction "1_1") (pintype "passive"))
      (node (ref "D7") (pin "C") (pinfunction "C_C") (pintype "passive"))
      (node (ref "D9") (pin "A") (pinfunction "A_A") (pintype "passive"))
      (node (ref "R13") (pin "1") (pinfunction "1_1") (pintype "passive"))
      (node (ref "U$1") (pin "18") (pinfunction "C4_18") (pintype "bidirectional"))
    )
    (net (code "22") (name "/CELL_5") (class "Default")
      (node (ref "CELL-IN") (pin "4") (pinfunction "S_4") (pintype "passive"))
      (node (ref "CELL-MEAS") (pin "4") (pinfunction "S_4") (pintype "passive"))
      (node (ref "D12") (pin "C") (pinfunction "C_C") (pintype "passive"))
      (node (ref "Q5") (pin "2") (pinfunction "S_2") (pintype "passive"))
      (node (ref "R17") (pin "2") (pinfunction "2_2") (pintype "passive"))
      (node (ref "R22") (pin "P$2") (pinfunction "2_P$2") (pintype "passive"))
    )
    (net (code "23") (name "/CELL_5_BAL") (class "Default")
      (node (ref "R20") (pin "1") (pinfunction "1_1") (pintype "passive"))
      (node (ref "U$1") (pin "17") (pinfunction "S5_17") (pintype "bidirectional"))
    )
    (net (code "24") (name "/CELL_5_FILTER") (class "Default")
      (node (ref "C5") (pin "1") (pinfunction "1_1") (pintype "passive"))
      (node (ref "D11") (pin "A") (pinfunction "A_A") (pintype "passive"))
      (node (ref "D9") (pin "C") (pinfunction "C_C") (pintype "passive"))
      (node (ref "R17") (pin "1") (pinfunction "1_1") (pintype "passive"))
      (node (ref "U$1") (pin "16") (pinfunction "C5_16") (pintype "bidirectional"))
    )
    (net (code "25") (name "/CELL_6") (class "Default")
      (node (ref "CELL-IN") (pin "3") (pinfunction "S_3") (pintype "passive"))
      (node (ref "CELL-MEAS") (pin "3") (pinfunction "S_3") (pintype "passive"))
      (node (ref "D14") (pin "C") (pinfunction "C_C") (pintype "passive"))
      (node (ref "Q6") (pin "2") (pinfunction "S_2") (pintype "passive"))
      (node (ref "R21") (pin "2") (pinfunction "2_2") (pintype "passive"))
      (node (ref "R26") (pin "P$2") (pinfunction "2_P$2") (pintype "passive"))
    )
    (net (code "26") (name "/CELL_6_BAL") (class "Default")
      (node (ref "R24") (pin "1") (pinfunction "1_1") (pintype "passive"))
      (node (ref "U$1") (pin "15") (pinfunction "S6_15") (pintype "bidirectional"))
    )
    (net (code "27") (name "/CELL_6_FILTER") (class "Default")
      (node (ref "C6") (pin "1") (pinfunction "1_1") (pintype "passive"))
      (node (ref "D11") (pin "C") (pinfunction "C_C") (pintype "passive"))
      (node (ref "D13") (pin "A") (pinfunction "A_A") (pintype "passive"))
      (node (ref "R21") (pin "1") (pinfunction "1_1") (pintype "passive"))
      (node (ref "U$1") (pin "14") (pinfunction "C6_14") (pintype "bidirectional"))
    )
    (net (code "28") (name "/CELL_7") (class "Default")
      (node (ref "CELL-IN") (pin "2") (pinfunction "S_2") (pintype "passive"))
      (node (ref "CELL-MEAS") (pin "2") (pinfunction "S_2") (pintype "passive"))
      (node (ref "D16") (pin "C") (pinfunction "C_C") (pintype "passive"))
      (node (ref "Q7") (pin "2") (pinfunction "S_2") (pintype "passive"))
      (node (ref "R25") (pin "2") (pinfunction "2_2") (pintype "passive"))
      (node (ref "R30") (pin "P$2") (pinfunction "2_P$2") (pintype "passive"))
    )
    (net (code "29") (name "/CELL_7_BAL") (class "Default")
      (node (ref "R28") (pin "1") (pinfunction "1_1") (pintype "passive"))
      (node (ref "U$1") (pin "13") (pinfunction "S7_13") (pintype "bidirectional"))
    )
    (net (code "30") (name "/CELL_7_FILTER") (class "Default")
      (node (ref "C7") (pin "1") (pinfunction "1_1") (pintype "passive"))
      (node (ref "D13") (pin "C") (pinfunction "C_C") (pintype "passive"))
      (node (ref "D15") (pin "A") (pinfunction "A_A") (pintype "passive"))
      (node (ref "R25") (pin "1") (pinfunction "1_1") (pintype "passive"))
      (node (ref "U$1") (pin "12") (pinfunction "C7_12") (pintype "bidirectional"))
    )
    (net (code "31") (name "/CELL_8") (class "Default")
      (node (ref "CELL-IN") (pin "1") (pinfunction "S_1") (pintype "passive"))
      (node (ref "CELL-MEAS") (pin "1") (pinfunction "S_1") (pintype "passive"))
      (node (ref "L1") (pin "1") (pinfunction "1_1") (pintype "passive"))
      (node (ref "Q8") (pin "2") (pinfunction "S_2") (pintype "passive"))
      (node (ref "R29") (pin "2") (pinfunction "2_2") (pintype "passive"))
      (node (ref "U$2") (pin "4_1") (pinfunction "IP+_4_1") (pintype "bidirectional"))
      (node (ref "U$2") (pin "4_10") (pinfunction "IP+_4_10") (pintype "bidirectional"))
      (node (ref "U$2") (pin "4_11") (pinfunction "IP+_4_11") (pintype "bidirectional"))
      (node (ref "U$2") (pin "4_12") (pinfunction "IP+_4_12") (pintype "bidirectional"))
      (node (ref "U$2") (pin "4_13") (pinfunction "IP+_4_13") (pintype "bidirectional"))
      (node (ref "U$2") (pin "4_14") (pinfunction "IP+_4_14") (pintype "bidirectional"))
      (node (ref "U$2") (pin "4_15") (pinfunction "IP+_4_15") (pintype "bidirectional"))
      (node (ref "U$2") (pin "4_16") (pinfunction "IP+_4_16") (pintype "bidirectional"))
      (node (ref "U$2") (pin "4_2") (pinfunction "IP+_4_2") (pintype "bidirectional"))
      (node (ref "U$2") (pin "4_3") (pinfunction "IP+_4_3") (pintype "bidirectional"))
      (node (ref "U$2") (pin "4_4") (pinfunction "IP+_4_4") (pintype "bidirectional"))
      (node (ref "U$2") (pin "4_5") (pinfunction "IP+_4_5") (pintype "bidirectional"))
      (node (ref "U$2") (pin "4_6") (pinfunction "IP+_4_6") (pintype "bidirectional"))
      (node (ref "U$2") (pin "4_7") (pinfunction "IP+_4_7") (pintype "bidirectional"))
      (node (ref "U$2") (pin "4_8") (pinfunction "IP+_4_8") (pintype "bidirectional"))
      (node (ref "U$2") (pin "4_9") (pinfunction "IP+_4_9") (pintype "bidirectional"))
      (node (ref "U$2") (pin "4_B") (pinfunction "IP+_4_B") (pintype "bidirectional"))
      (node (ref "U$2") (pin "4_T") (pinfunction "IP+_4_T") (pintype "bidirectional"))
      (node (ref "V_ARRAY") (pin "P$1") (pinfunction "P$1_P$1") (pintype "bidirectional"))
    )
    (net (code "32") (name "/CELL_8_BAL") (class "Default")
      (node (ref "R32") (pin "1") (pinfunction "1_1") (pintype "passive"))
      (node (ref "U$1") (pin "11") (pinfunction "S8_11") (pintype "bidirectional"))
    )
    (net (code "33") (name "/CELL_8_FILTER") (class "Default")
      (node (ref "C8") (pin "1") (pinfunction "1_1") (pintype "passive"))
      (node (ref "D15") (pin "C") (pinfunction "C_C") (pintype "passive"))
      (node (ref "R29") (pin "1") (pinfunction "1_1") (pintype "passive"))
      (node (ref "U$1") (pin "10") (pinfunction "C8_10") (pintype "bidirectional"))
      (node (ref "U$1") (pin "2") (pinfunction "C12_2") (pintype "bidirectional"))
      (node (ref "U$1") (pin "4") (pinfunction "C11_4") (pintype "bidirectional"))
      (node (ref "U$1") (pin "6") (pinfunction "C10_6") (pintype "bidirectional"))
      (node (ref "U$1") (pin "8") (pinfunction "C9_8") (pintype "bidirectional"))
    )
    (net (code "34") (name "/CHARGER+") (class "Default")
      (node (ref "J1") (pin "PIN1-1") (pinfunction "1-1_PIN1-1") (pintype "bidirectional"))
      (node (ref "J1") (pin "PIN1-2") (pinfunction "1-2_PIN1-2") (pintype "bidirectional"))
      (node (ref "JP4") (pin "4") (pinfunction "4_4") (pintype "passive"))
      (node (ref "Q9") (pin "2") (pinfunction "D_2") (pintype "bidirectional"))
      (node (ref "Q9") (pin "4") (pinfunction "P$1_4") (pintype "bidirectional"))
      (node (ref "R43") (pin "2") (pinfunction "2_2") (pintype "passive"))
      (node (ref "U$10") (pin "+") (pinfunction "+_+") (pintype "passive"))
      (node (ref "U$11") (pin "+") (pinfunction "+_+") (pintype "passive"))
    )
    (net (code "35") (name "/CHARGER_CTL") (class "Default")
      (node (ref "U$12") (pin "P$1") (pinfunction "INP_P$1") (pintype "bidirectional"))
      (node (ref "U$13") (pin "8.0") (pinfunction "P8.0_8.0") (pintype "bidirectional"))
    )
    (net (code "36") (name "/CHARGER_I_MEAS") (class "Default")
      (node (ref "U$13") (pin "5.2") (pinfunction "P5.2_5.2") (pintype "bidirectional"))
      (node (ref "U$4") (pin "3") (pinfunction "VIOUT_3") (pintype "bidirectional"))
    )
    (net (code "37") (name "/ESTOP_1") (class "Default")
      (node (ref "JP3") (pin "2") (pinfunction "2_2") (pintype "passive"))
      (node (ref "R45") (pin "1") (pinfunction "1_1") (pintype "passive"))
      (node (ref "U$13") (pin "1.5") (pinfunction "P1.5_1.5") (pintype "bidirectional"))
    )
    (net (code "38") (name "/ESTOP_2") (class "Default")
      (node (ref "JP2") (pin "2") (pinfunction "2_2") (pintype "passive"))
      (node (ref "R46") (pin "1") (pinfunction "1_1") (pintype "passive"))
      (node (ref "U$13") (pin "1.6") (pinfunction "P1.6_1.6") (pintype "bidirectional"))
    )
    (net (code "39") (name "/FAN_CTL_1") (class "Default")
      (node (ref "Q12") (pin "1") (pinfunction "G_1") (pintype "passive"))
      (node (ref "U$13") (pin "2.4") (pinfunction "P2.4_2.4") (pintype "bidirectional"))
    )
    (net (code "40") (name "/FAN_CTL_2") (class "Default")
      (node (ref "Q13") (pin "1") (pinfunction "G_1") (pintype "passive"))
      (node (ref "U$13") (pin "2.5") (pinfunction "P2.5_2.5") (pintype "bidirectional"))
    )
    (net (code "41") (name "/FAN_CTL_3") (class "Default")
      (node (ref "Q14") (pin "1") (pinfunction "G_1") (pintype "passive"))
      (node (ref "U$13") (pin "2.6") (pinfunction "P2.6_2.6") (pintype "bidirectional"))
    )
    (net (code "42") (name "/FAN_CTL_4") (class "Default")
      (node (ref "Q15") (pin "1") (pinfunction "G_1") (pintype "passive"))
      (node (ref "U$13") (pin "2.7") (pinfunction "P2.7_2.7") (pintype "bidirectional"))
    )
    (net (code "43") (name "/FAN_TACH_1") (class "Default")
      (node (ref "U$13") (pin "5.0") (pinfunction "P5.0_5.0") (pintype "bidirectional"))
      (node (ref "X1") (pin "3") (pinfunction "S_3") (pintype "passive"))
    )
    (net (code "44") (name "/FAN_TACH_2") (class "Default")
      (node (ref "U$13") (pin "3.3") (pinfunction "P3.3_3.3") (pintype "bidirectional"))
      (node (ref "X2") (pin "3") (pinfunction "S_3") (pintype "passive"))
    )
    (net (code "45") (name "/FAN_TACH_3") (class "Default")
      (node (ref "U$13") (pin "3.2") (pinfunction "P3.2_3.2") (pintype "bidirectional"))
      (node (ref "X3") (pin "3") (pinfunction "S_3") (pintype "passive"))
    )
    (net (code "46") (name "/FAN_TACH_4") (class "Default")
      (node (ref "U$13") (pin "3.0") (pinfunction "P3.0_3.0") (pintype "bidirectional"))
      (node (ref "X4") (pin "3") (pinfunction "S_3") (pintype "passive"))
    )
    (net (code "47") (name "/GAUGE_ON") (class "Default")
      (node (ref "GAUGE_ON") (pin "2") (pinfunction "2_2") (pintype "passive"))
      (node (ref "IC2") (pin "P$10") (pinfunction "/G_P$10") (pintype "bidirectional"))
      (node (ref "R57") (pin "2") (pinfunction "2_2") (pintype "passive"))
      (node (ref "S2") (pin "3") (pinfunction "2_3") (pintype "passive"))
      (node (ref "U$13") (pin "6.6") (pinfunction "P6.6_6.6") (pintype "bidirectional"))
    )
    (net (code "48") (name "/LCD_DB[0]") (class "Default")
      (node (ref "JP5") (pin "7") (pinfunction "7_7") (pintype "passive"))
      (node (ref "U$13") (pin "4.0") (pinfunction "P4.0_4.0") (pintype "bidirectional"))
    )
    (net (code "49") (name "/LCD_DB[1]") (class "Default")
      (node (ref "JP5") (pin "8") (pinfunction "8_8") (pintype "passive"))
      (node (ref "U$13") (pin "4.1") (pinfunction "P4.1_4.1") (pintype "bidirectional"))
    )
    (net (code "50") (name "/LCD_DB[2]") (class "Default")
      (node (ref "JP5") (pin "9") (pinfunction "9_9") (pintype "passive"))
      (node (ref "U$13") (pin "4.2") (pinfunction "P4.2_4.2") (pintype "bidirectional"))
    )
    (net (code "51") (name "/LCD_DB[3]") (class "Default")
      (node (ref "JP5") (pin "10") (pinfunction "10_10") (pintype "passive"))
      (node (ref "U$13") (pin "4.3") (pinfunction "P4.3_4.3") (pintype "bidirectional"))
    )
    (net (code "52") (name "/LCD_DB[4]") (class "Default")
      (node (ref "JP5") (pin "11") (pinfunction "11_11") (pintype "passive"))
      (node (ref "U$13") (pin "4.4") (pinfunction "P4.4_4.4") (pintype "bidirectional"))
    )
    (net (code "53") (name "/LCD_DB[5]") (class "Default")
      (node (ref "JP5") (pin "12") (pinfunction "12_12") (pintype "passive"))
      (node (ref "U$13") (pin "4.5") (pinfunction "P4.5_4.5") (pintype "bidirectional"))
    )
    (net (code "54") (name "/LCD_DB[6]") (class "Default")
      (node (ref "JP5") (pin "13") (pinfunction "13_13") (pintype "passive"))
      (node (ref "U$13") (pin "4.6") (pinfunction "P4.6_4.6") (pintype "bidirectional"))
    )
    (net (code "55") (name "/LCD_DB[7]") (class "Default")
      (node (ref "JP5") (pin "14") (pinfunction "14_14") (pintype "passive"))
      (node (ref "U$13") (pin "4.7") (pinfunction "P4.7_4.7") (pintype "bidirectional"))
    )
    (net (code "56") (name "/LCD_EN") (class "Default")
      (node (ref "JP5") (pin "6") (pinfunction "6_6") (pintype "passive"))
      (node (ref "U$13") (pin "3.7") (pinfunction "P3.7_3.7") (pintype "bidirectional"))
    )
    (net (code "57") (name "/LCD_RS") (class "Default")
      (node (ref "JP5") (pin "4") (pinfunction "4_4") (pintype "passive"))
      (node (ref "U$13") (pin "3.5") (pinfunction "P3.5_3.5") (pintype "bidirectional"))
    )
    (net (code "58") (name "/LCD_RW") (class "Default")
      (node (ref "JP5") (pin "5") (pinfunction "5_5") (pintype "passive"))
      (node (ref "U$13") (pin "3.6") (pinfunction "P3.6_3.6") (pintype "bidirectional"))
    )
    (net (code "59") (name "/LCD_VBACK") (class "Default")
      (node (ref "JP5") (pin "3") (pinfunction "3_3") (pintype "passive"))
      (node (ref "RV1") (pin "1") (pinfunction "S_1") (pintype "passive"))
    )
    (net (code "60") (name "/LED_CLR") (class "Default")
      (node (ref "IC2") (pin "P$9") (pinfunction "/CLR_P$9") (pintype "bidirectional"))
      (node (ref "U$13") (pin "10.0") (pinfunction "P10.0_10.0") (pintype "bidirectional"))
    )
    (net (code "61") (name "/LED_RCK") (class "Default")
      (node (ref "IC2") (pin "P$12") (pinfunction "RCK_P$12") (pintype "bidirectional"))
      (node (ref "U$13") (pin "10.1") (pinfunction "P10.1_10.1") (pintype "bidirectional"))
    )
    (net (code "62") (name "/LED_SER_IN") (class "Default")
      (node (ref "IC2") (pin "P$2") (pinfunction "SER_IN_P$2") (pintype "bidirectional"))
      (node (ref "U$13") (pin "10.2") (pinfunction "P10.2_10.2") (pintype "bidirectional"))
    )
    (net (code "63") (name "/LED_SRCK") (class "Default")
      (node (ref "IC2") (pin "P$19") (pinfunction "SRCK_P$19") (pintype "bidirectional"))
      (node (ref "U$13") (pin "10.3") (pinfunction "P10.3_10.3") (pintype "bidirectional"))
    )
    (net (code "64") (name "/LOGIC_POWER") (class "Default")
      (node (ref "F1") (pin "2") (pinfunction "2_2") (pintype "bidirectional"))
      (node (ref "OKI-78SR") (pin "1") (pinfunction "VI_1") (pintype "bidirectional"))
      (node (ref "OKI-78SR1") (pin "1") (pinfunction "VI_1") (pintype "bidirectional"))
    )
    (net (code "65") (name "/N$115") (class "Default")
      (node (ref "JP5") (pin "15") (pinfunction "15_15") (pintype "passive"))
    )
    (net (code "66") (name "/N$116") (class "Default")
      (node (ref "JP5") (pin "16") (pinfunction "16_16") (pintype "passive"))
    )
    (net (code "67") (name "/PACK_GATE") (class "Default")
      (node (ref "U$13") (pin "6.0") (pinfunction "P6.0_6.0") (pintype "bidirectional"))
      (node (ref "U$8") (pin "4") (pinfunction "IN_4") (pintype "bidirectional"))
    )
    (net (code "68") (name "/PACK_I_MEAS") (class "Default")
      (node (ref "U$13") (pin "5.5") (pinfunction "P5.5_5.5") (pintype "bidirectional"))
      (node (ref "U$2") (pin "3") (pinfunction "VIOUT_3") (pintype "bidirectional"))
    )
    (net (code "69") (name "/SER_IN") (class "Default")
      (node (ref "U$13") (pin "9.6") (pinfunction "P9.6_9.6") (pintype "bidirectional"))
      (node (ref "U$15") (pin "RO") (pinfunction "R0_RO") (pintype "bidirectional"))
    )
    (net (code "70") (name "/SER_OUT") (class "Default")
      (node (ref "U$13") (pin "9.7") (pinfunction "P9.7_9.7") (pintype "bidirectional"))
      (node (ref "U$15") (pin "DI") (pinfunction "DI_DI") (pintype "bidirectional"))
    )
    (net (code "71") (name "/SUPPLY_CTL") (class "Default")
      (node (ref "JP4") (pin "6") (pinfunction "6_6") (pintype "passive"))
      (node (ref "U$13") (pin "2.3") (pinfunction "P2.3_2.3") (pintype "bidirectional"))
    )
    (net (code "72") (name "/SUPPLY_DC_OK") (class "Default")
      (node (ref "JP4") (pin "1") (pinfunction "1_1") (pintype "passive"))
      (node (ref "U$13") (pin "1.7") (pinfunction "P1.7_1.7") (pintype "bidirectional"))
    )
    (net (code "73") (name "/TEMP_1") (class "Default")
      (node (ref "C11") (pin "1") (pinfunction "1_1") (pintype "passive"))
      (node (ref "R34") (pin "1") (pinfunction "1_1") (pintype "passive"))
      (node (ref "U$1") (pin "28") (pinfunction "VTEMP1_28") (pintype "bidirectional"))
    )
    (net (code "74") (name "/TEMP_2") (class "Default")
      (node (ref "C12") (pin "1") (pinfunction "1_1") (pintype "passive"))
      (node (ref "R36") (pin "1") (pinfunction "1_1") (pintype "passive"))
      (node (ref "U$1") (pin "29") (pinfunction "VTEMP2_29") (pintype "bidirectional"))
    )
    (net (code "75") (name "/V_CHECK_ARRAY") (class "Default")
      (node (ref "R41") (pin "1") (pinfunction "1_1") (pintype "passive"))
      (node (ref "R42") (pin "2") (pinfunction "2_2") (pintype "passive"))
      (node (ref "U$13") (pin "5.3") (pinfunction "P5.3_5.3") (pintype "bidirectional"))
    )
    (net (code "76") (name "/V_CHECK_CHARGER_IN") (class "Default")
      (node (ref "R43") (pin "1") (pinfunction "1_1") (pintype "passive"))
      (node (ref "R44") (pin "2") (pinfunction "2_2") (pintype "passive"))
      (node (ref "U$13") (pin "5.1") (pinfunction "P5.1_5.1") (pintype "bidirectional"))
    )
    (net (code "77") (name "/V_CHECK_OUT") (class "Default")
      (node (ref "R38") (pin "2") (pinfunction "2_2") (pintype "passive"))
      (node (ref "R39") (pin "1") (pinfunction "1_1") (pintype "passive"))
      (node (ref "U$13") (pin "5.4") (pinfunction "P5.4_5.4") (pintype "bidirectional"))
    )
    (net (code "78") (name "5V") (class "Default")
      (node (ref "BUZZER_1") (pin "+") (pinfunction "1_+") (pintype "passive"))
      (node (ref "BUZZER_2") (pin "-") (pinfunction "2_-") (pintype "passive"))
      (node (ref "C18") (pin "1") (pinfunction "1_1") (pintype "passive"))
      (node (ref "C21") (pin "1") (pinfunction "1_1") (pintype "passive"))
      (node (ref "C22") (pin "1") (pinfunction "1_1") (pintype "passive"))
      (node (ref "IC2") (pin "P$1") (pinfunction "VCC_P$1") (pintype "bidirectional"))
      (node (ref "JP5") (pin "2") (pinfunction "2_2") (pintype "passive"))
      (node (ref "L3") (pin "2") (pinfunction "2_2") (pintype "passive"))
      (node (ref "R45") (pin "2") (pinfunction "2_2") (pintype "passive"))
      (node (ref "R46") (pin "2") (pinfunction "2_2") (pintype "passive"))
      (node (ref "R47") (pin "2") (pinfunction "2_2") (pintype "passive"))
      (node (ref "R48") (pin "2") (pinfunction "2_2") (pintype "passive"))
      (node (ref "R49") (pin "2") (pinfunction "2_2") (pintype "passive"))
      (node (ref "R50") (pin "2") (pinfunction "2_2") (pintype "passive"))
      (node (ref "R51") (pin "2") (pinfunction "2_2") (pintype "passive"))
      (node (ref "R52") (pin "2") (pinfunction "2_2") (pintype "passive"))
      (node (ref "R53") (pin "2") (pinfunction "2_2") (pintype "passive"))
      (node (ref "R54") (pin "2") (pinfunction "2_2") (pintype "passive"))
      (node (ref "R55") (pin "2") (pinfunction "2_2") (pintype "passive"))
      (node (ref "R56") (pin "2") (pinfunction "2_2") (pintype "passive"))
      (node (ref "R57") (pin "1") (pinfunction "1_1") (pintype "passive"))
      (node (ref "R58") (pin "1") (pinfunction "1_1") (pintype "passive"))
      (node (ref "R59") (pin "1") (pinfunction "1_1") (pintype "passive"))
      (node (ref "R60") (pin "1") (pinfunction "1_1") (pintype "passive"))
      (node (ref "R61") (pin "1") (pinfunction "1_1") (pintype "passive"))
      (node (ref "R62") (pin "1") (pinfunction "1_1") (pintype "passive"))
      (node (ref "R63") (pin "1") (pinfunction "1_1") (pintype "passive"))
      (node (ref "R64") (pin "1") (pinfunction "1_1") (pintype "passive"))
      (node (ref "R65") (pin "1") (pinfunction "1_1") (pintype "passive"))
      (node (ref "R66") (pin "1") (pinfunction "1_1") (pintype "passive"))
      (node (ref "R67") (pin "1") (pinfunction "1_1") (pintype "passive"))
      (node (ref "RV1") (pin "3") (pinfunction "A_3") (pintype "passive"))
      (node (ref "U$13") (pin "5V_1") (pinfunction "5V_1_5V_1") (pintype "bidirectional"))
      (node (ref "U$13") (pin "5V_2") (pinfunction "5V_2_5V_2") (pintype "bidirectional"))
      (node (ref "U$13") (pin "5V_3") (pinfunction "5V_3_5V_3") (pintype "bidirectional"))
      (node (ref "U$13") (pin "5V_4") (pinfunction "5V_4_5V_4") (pintype "bidirectional"))
      (node (ref "U$15") (pin "VCC") (pinfunction "VCC_VCC") (pintype "bidirectional"))
      (node (ref "U$2") (pin "1") (pinfunction "VCC_1") (pintype "bidirectional"))
      (node (ref "U$4") (pin "1") (pinfunction "VCC_1") (pintype "bidirectional"))
    )
    (net (code "79") (name "GND") (class "Default")
      (node (ref "C1") (pin "2") (pinfunction "2_2") (pintype "passive"))
      (node (ref "C10") (pin "2") (pinfunction "2_2") (pintype "passive"))
      (node (ref "C11") (pin "2") (pinfunction "2_2") (pintype "passive"))
      (node (ref "C12") (pin "2") (pinfunction "2_2") (pintype "passive"))
      (node (ref "C13") (pin "2") (pinfunction "2_2") (pintype "passive"))
      (node (ref "C14") (pin "2") (pinfunction "2_2") (pintype "passive"))
      (node (ref "C16") (pin "2") (pinfunction "2_2") (pintype "passive"))
      (node (ref "C17") (pin "2") (pinfunction "2_2") (pintype "passive"))
      (node (ref "C18") (pin "2") (pinfunction "2_2") (pintype "passive"))
      (node (ref "C19") (pin "2") (pinfunction "2_2") (pintype "passive"))
      (node (ref "C2") (pin "2") (pinfunction "2_2") (pintype "passive"))
      (node (ref "C20") (pin "2") (pinfunction "2_2") (pintype "passive"))
      (node (ref "C21") (pin "2") (pinfunction "2_2") (pintype "passive"))
      (node (ref "C22") (pin "2") (pinfunction "2_2") (pintype "passive"))
      (node (ref "C3") (pin "2") (pinfunction "2_2") (pintype "passive"))
      (node (ref "C4") (pin "2") (pinfunction "2_2") (pintype "passive"))
      (node (ref "C5") (pin "2") (pinfunction "2_2") (pintype "passive"))
      (node (ref "C6") (pin "2") (pinfunction "2_2") (pintype "passive"))
      (node (ref "C7") (pin "2") (pinfunction "2_2") (pintype "passive"))
      (node (ref "C8") (pin "2") (pinfunction "2_2") (pintype "passive"))
      (node (ref "C9") (pin "2") (pinfunction "2_2") (pintype "passive"))
      (node (ref "CELL-IN") (pin "9") (pinfunction "S_9") (pintype "passive"))
      (node (ref "CELL-MEAS") (pin "9") (pinfunction "S_9") (pintype "passive"))
      (node (ref "D1") (pin "A") (pinfunction "A_A") (pintype "passive"))
      (node (ref "D17") (pin "A") (pinfunction "A_A") (pintype "passive"))
      (node (ref "D18") (pin "A") (pinfunction "A_A") (pintype "passive"))
      (node (ref "D19") (pin "A") (pinfunction "A_A") (pintype "passive"))
      (node (ref "D2") (pin "C") (pinfunction "C_C") (pintype "passive"))
      (node (ref "GAUGE_ON") (pin "1") (pinfunction "1_1") (pintype "passive"))
      (node (ref "IC1") (pin "4") (pinfunction "V-_4") (pintype "power_in"))
      (node (ref "IC2") (pin "P$20") (pinfunction "GND_P$20") (pintype "bidirectional"))
      (node (ref "J1") (pin "PIN2-1") (pinfunction "2-1_PIN2-1") (pintype "bidirectional"))
      (node (ref "J1") (pin "PIN2-2") (pinfunction "2-2_PIN2-2") (pintype "bidirectional"))
      (node (ref "JP2") (pin "1") (pinfunction "1_1") (pintype "passive"))
      (node (ref "JP3") (pin "1") (pinfunction "1_1") (pintype "passive"))
      (node (ref "JP4") (pin "2") (pinfunction "2_2") (pintype "passive"))
      (node (ref "JP4") (pin "3") (pinfunction "3_3") (pintype "passive"))
      (node (ref "JP4") (pin "5") (pinfunction "5_5") (pintype "passive"))
      (node (ref "JP5") (pin "1") (pinfunction "1_1") (pintype "passive"))
      (node (ref "OKI-78SR") (pin "2") (pinfunction "GND_2") (pintype "bidirectional"))
      (node (ref "OKI-78SR1") (pin "2") (pinfunction "GND_2") (pintype "bidirectional"))
      (node (ref "Q10") (pin "2") (pinfunction "S_2") (pintype "passive"))
      (node (ref "Q11") (pin "2") (pinfunction "S_2") (pintype "passive"))
      (node (ref "Q12") (pin "2") (pinfunction "S_2") (pintype "passive"))
      (node (ref "Q13") (pin "2") (pinfunction "S_2") (pintype "passive"))
      (node (ref "Q14") (pin "2") (pinfunction "S_2") (pintype "passive"))
      (node (ref "Q15") (pin "2") (pinfunction "S_2") (pintype "passive"))
      (node (ref "R2") (pin "P$2") (pinfunction "2_P$2") (pintype "passive"))
      (node (ref "R39") (pin "2") (pinfunction "2_2") (pintype "passive"))
      (node (ref "R40") (pin "2") (pinfunction "2_2") (pintype "passive"))
      (node (ref "R42") (pin "1") (pinfunction "1_1") (pintype "passive"))
      (node (ref "R44") (pin "1") (pinfunction "1_1") (pintype "passive"))
      (node (ref "RV1") (pin "2") (pinfunction "E_2") (pintype "passive"))
      (node (ref "S1") (pin "3") (pinfunction "S_3") (pintype "passive"))
      (node (ref "S2") (pin "1") (pinfunction "1_1") (pintype "passive"))
      (node (ref "THERM_1") (pin "2") (pinfunction "S_2") (pintype "passive"))
      (node (ref "THERM_2") (pin "2") (pinfunction "S_2") (pintype "passive"))
      (node (ref "U$1") (pin "26") (pinfunction "V-_26") (pintype "bidirectional"))
      (node (ref "U$1") (pin "32") (pinfunction "TOS_32") (pintype "bidirectional"))
      (node (ref "U$1") (pin "35") (pinfunction "GPIO1_35") (pintype "bidirectional"))
      (node (ref "U$1") (pin "36") (pinfunction "GPIO2_36") (pintype "bidirectional"))
      (node (ref "U$1") (pin "37") (pinfunction "A0_37") (pintype "bidirectional"))
      (node (ref "U$1") (pin "38") (pinfunction "A1_38") (pintype "bidirectional"))
      (node (ref "U$1") (pin "39") (pinfunction "A2_39") (pintype "bidirectional"))
      (node (ref "U$1") (pin "40") (pinfunction "A3_40") (pintype "bidirectional"))
      (node (ref "U$10") (pin "GND") (pinfunction "-_GND") (pintype "passive"))
      (node (ref "U$11") (pin "GND") (pinfunction "-_GND") (pintype "passive"))
      (node (ref "U$12") (pin "P$2") (pinfunction "GND_P$2") (pintype "bidirectional"))
      (node (ref "U$12") (pin "P$4") (pinfunction "GND_P$4") (pintype "bidirectional"))
      (node (ref "U$12") (pin "P$9") (pinfunction "GND_P$9") (pintype "bidirectional"))
      (node (ref "U$13") (pin "GND_1") (pinfunction "GND1_GND_1") (pintype "bidirectional"))
      (node (ref "U$13") (pin "GND_2") (pinfunction "GND2_GND_2") (pintype "bidirectional"))
      (node (ref "U$13") (pin "GND_3") (pinfunction "GND3_GND_3") (pintype "bidirectional"))
      (node (ref "U$13") (pin "GND_4") (pinfunction "GND4_GND_4") (pintype "bidirectional"))
      (node (ref "U$13") (pin "GND_5") (pinfunction "GND5_GND_5") (pintype "bidirectional"))
      (node (ref "U$13") (pin "GND_6") (pinfunction "GND6_GND_6") (pintype "bidirectional"))
      (node (ref "U$13") (pin "GND_7") (pinfunction "GND7_GND_7") (pintype "bidirectional"))
      (node (ref "U$13") (pin "GND_8") (pinfunction "GND8_GND_8") (pintype "bidirectional"))
      (node (ref "U$14") (pin "7") (pinfunction "7_7") (pintype "bidirectional"))
      (node (ref "U$14") (pin "8") (pinfunction "8_8") (pintype "bidirectional"))
      (node (ref "U$15") (pin "GND") (pinfunction "GND_GND") (pintype "bidirectional"))
      (node (ref "U$2") (pin "2") (pinfunction "GND_2") (pintype "bidirectional"))
      (node (ref "U$3") (pin "GND") (pinfunction "-_GND") (pintype "passive"))
      (node (ref "U$4") (pin "2") (pinfunction "GND_2") (pintype "bidirectional"))
      (node (ref "U$6") (pin "GND") (pinfunction "-_GND") (pintype "passive"))
      (node (ref "U$7") (pin "GND") (pinfunction "-_GND") (pintype "passive"))
      (node (ref "U$8") (pin "1") (pinfunction "GND_1") (pintype "bidirectional"))
      (node (ref "U$9") (pin "P$1") (pinfunction "A_P$1") (pintype "passive"))
      (node (ref "U$9") (pin "P$3") (pinfunction "A_P$3") (pintype "passive"))
      (node (ref "V_OUT1") (pin "P$1") (pinfunction "P$1_P$1") (pintype "bidirectional"))
    )
    (net (code "80") (name "Net-(BUZZER_1-2)") (class "Default")
      (node (ref "BUZZER_1") (pin "-") (pinfunction "2_-") (pintype "passive"))
      (node (ref "Q11") (pin "3") (pinfunction "D_3") (pintype "passive"))
    )
    (net (code "81") (name "Net-(BUZZER_2-1)") (class "Default")
      (node (ref "BUZZER_2") (pin "+") (pinfunction "1_+") (pintype "passive"))
      (node (ref "Q10") (pin "3") (pinfunction "D_3") (pintype "passive"))
    )
    (net (code "82") (name "Net-(D2-PadA)") (class "Default")
      (node (ref "D2") (pin "A") (pinfunction "A_A") (pintype "passive"))
      (node (ref "R3") (pin "2") (pinfunction "2_2") (pintype "passive"))
    )
    (net (code "83") (name "Net-(D4-PadA)") (class "Default")
      (node (ref "D4") (pin "A") (pinfunction "A_A") (pintype "passive"))
      (node (ref "R7") (pin "2") (pinfunction "2_2") (pintype "passive"))
    )
    (net (code "84") (name "Net-(D6-PadA)") (class "Default")
      (node (ref "D6") (pin "A") (pinfunction "A_A") (pintype "passive"))
      (node (ref "R11") (pin "2") (pinfunction "2_2") (pintype "passive"))
    )
    (net (code "85") (name "Net-(D8-PadA)") (class "Default")
      (node (ref "D8") (pin "A") (pinfunction "A_A") (pintype "passive"))
      (node (ref "R15") (pin "2") (pinfunction "2_2") (pintype "passive"))
    )
    (net (code "86") (name "Net-(D10-PadA)") (class "Default")
      (node (ref "D10") (pin "A") (pinfunction "A_A") (pintype "passive"))
      (node (ref "R19") (pin "2") (pinfunction "2_2") (pintype "passive"))
    )
    (net (code "87") (name "Net-(D12-PadA)") (class "Default")
      (node (ref "D12") (pin "A") (pinfunction "A_A") (pintype "passive"))
      (node (ref "R23") (pin "2") (pinfunction "2_2") (pintype "passive"))
    )
    (net (code "88") (name "Net-(D14-PadA)") (class "Default")
      (node (ref "D14") (pin "A") (pinfunction "A_A") (pintype "passive"))
      (node (ref "R27") (pin "2") (pinfunction "2_2") (pintype "passive"))
    )
    (net (code "89") (name "Net-(D16-PadA)") (class "Default")
      (node (ref "D16") (pin "A") (pinfunction "A_A") (pintype "passive"))
      (node (ref "R31") (pin "2") (pinfunction "2_2") (pintype "passive"))
    )
    (net (code "90") (name "Net-(D17-PadC)") (class "Default")
      (node (ref "D17") (pin "C") (pinfunction "C_C") (pintype "passive"))
      (node (ref "D18") (pin "C") (pinfunction "C_C") (pintype "passive"))
      (node (ref "D19") (pin "C") (pinfunction "C_C") (pintype "passive"))
      (node (ref "L1") (pin "2") (pinfunction "2_2") (pintype "passive"))
      (node (ref "R37") (pin "2") (pinfunction "2_2") (pintype "passive"))
    )
    (net (code "91") (name "Net-(D20-C)") (class "Default")
      (node (ref "C15") (pin "1") (pinfunction "1_1") (pintype "passive"))
      (node (ref "D20") (pin "3") (pinfunction "C_3") (pintype "passive"))
      (node (ref "U$12") (pin "P$6") (pinfunction "BOOST_P$6") (pintype "bidirectional"))
    )
    (net (code "92") (name "Net-(GAGUE_S-Pad1)") (class "Default")
      (node (ref "GAGUE_S") (pin "1") (pinfunction "1_1") (pintype "passive"))
      (node (ref "R58") (pin "2") (pinfunction "2_2") (pintype "passive"))
    )
    (net (code "93") (name "Net-(GAGUE_S-Pad2)") (class "Default")
      (node (ref "GAGUE_S") (pin "2") (pinfunction "2_2") (pintype "passive"))
      (node (ref "R59") (pin "2") (pinfunction "2_2") (pintype "passive"))
    )
    (net (code "94") (name "Net-(GAGUE_S-Pad3)") (class "Default")
      (node (ref "GAGUE_S") (pin "3") (pinfunction "3_3") (pintype "passive"))
      (node (ref "R60") (pin "2") (pinfunction "2_2") (pintype "passive"))
    )
    (net (code "95") (name "Net-(GAGUE_S-Pad4)") (class "Default")
      (node (ref "GAGUE_S") (pin "4") (pinfunction "4_4") (pintype "passive"))
      (node (ref "R61") (pin "2") (pinfunction "2_2") (pintype "passive"))
    )
    (net (code "96") (name "Net-(GAGUE_S-Pad5)") (class "Default")
      (node (ref "GAGUE_S") (pin "5") (pinfunction "5_5") (pintype "passive"))
      (node (ref "R62") (pin "2") (pinfunction "2_2") (pintype "passive"))
    )
    (net (code "97") (name "Net-(GAGUE_S-Pad6)") (class "Default")
      (node (ref "GAGUE_S") (pin "6") (pinfunction "6_6") (pintype "passive"))
      (node (ref "R63") (pin "2") (pinfunction "2_2") (pintype "passive"))
    )
    (net (code "98") (name "Net-(GAGUE_S-Pad7)") (class "Default")
      (node (ref "GAGUE_S") (pin "7") (pinfunction "7_7") (pintype "passive"))
      (node (ref "R64") (pin "2") (pinfunction "2_2") (pintype "passive"))
    )
    (net (code "99") (name "Net-(GAGUE_S-Pad8)") (class "Default")
      (node (ref "GAGUE_S") (pin "8") (pinfunction "8_8") (pintype "passive"))
      (node (ref "R65") (pin "2") (pinfunction "2_2") (pintype "passive"))
    )
    (net (code "100") (name "Net-(GAGUE_S-Pad9)") (class "Default")
      (node (ref "GAGUE_S") (pin "9") (pinfunction "9_9") (pintype "passive"))
      (node (ref "R66") (pin "2") (pinfunction "2_2") (pintype "passive"))
    )
    (net (code "101") (name "Net-(GAGUE_S-Pad10)") (class "Default")
      (node (ref "GAGUE_S") (pin "10") (pinfunction "10_10") (pintype "passive"))
      (node (ref "R67") (pin "2") (pinfunction "2_2") (pintype "passive"))
    )
    (net (code "102") (name "Net-(IC1A--IN)") (class "Default")
      (node (ref "IC1") (pin "1") (pinfunction "OUT_1") (pintype "output"))
      (node (ref "IC1") (pin "2") (pinfunction "-IN_2") (pintype "input"))
      (node (ref "R33") (pin "1") (pinfunction "1_1") (pintype "passive"))
    )
    (net (code "103") (name "Net-(IC1B--IN)") (class "Default")
      (node (ref "IC1") (pin "6") (pinfunction "-IN_6") (pintype "input"))
      (node (ref "IC1") (pin "7") (pinfunction "OUT_7") (pintype "output"))
      (node (ref "R35") (pin "1") (pinfunction "1_1") (pintype "passive"))
    )
    (net (code "104") (name "Net-(IC2-DRAIN0)") (class "Default")
      (node (ref "IC2") (pin "P$3") (pinfunction "DRAIN0_P$3") (pintype "bidirectional"))
      (node (ref "JP1") (pin "10") (pinfunction "10_10") (pintype "passive"))
      (node (ref "LED2") (pin "P$20") (pinfunction "20_P$20") (pintype "bidirectional"))
    )
    (net (code "105") (name "Net-(IC2-DRAIN1)") (class "Default")
      (node (ref "IC2") (pin "P$4") (pinfunction "DRAIN1_P$4") (pintype "bidirectional"))
      (node (ref "JP1") (pin "9") (pinfunction "9_9") (pintype "passive"))
      (node (ref "LED2") (pin "P$19") (pinfunction "19_P$19") (pintype "bidirectional"))
    )
    (net (code "106") (name "Net-(IC2-DRAIN2)") (class "Default")
      (node (ref "IC2") (pin "P$5") (pinfunction "DRAIN2_P$5") (pintype "bidirectional"))
      (node (ref "JP1") (pin "8") (pinfunction "8_8") (pintype "passive"))
      (node (ref "LED2") (pin "P$18") (pinfunction "18_P$18") (pintype "bidirectional"))
    )
    (net (code "107") (name "Net-(IC2-DRAIN3)") (class "Default")
      (node (ref "IC2") (pin "P$6") (pinfunction "DRAIN3_P$6") (pintype "bidirectional"))
      (node (ref "JP1") (pin "7") (pinfunction "7_7") (pintype "passive"))
      (node (ref "LED2") (pin "P$17") (pinfunction "17_P$17") (pintype "bidirectional"))
    )
    (net (code "108") (name "Net-(IC2-DRAIN4)") (class "Default")
      (node (ref "IC2") (pin "P$7") (pinfunction "DRAIN4_P$7") (pintype "bidirectional"))
      (node (ref "JP1") (pin "6") (pinfunction "6_6") (pintype "passive"))
      (node (ref "LED2") (pin "P$16") (pinfunction "16_P$16") (pintype "bidirectional"))
    )
    (net (code "109") (name "Net-(IC2-DRAIN5)") (class "Default")
      (node (ref "IC2") (pin "P$8") (pinfunction "DRAIN5_P$8") (pintype "bidirectional"))
      (node (ref "JP1") (pin "5") (pinfunction "5_5") (pintype "passive"))
      (node (ref "LED2") (pin "P$15") (pinfunction "15_P$15") (pintype "bidirectional"))
    )
    (net (code "110") (name "Net-(IC2-DRAIN6)") (class "Default")
      (node (ref "IC2") (pin "P$13") (pinfunction "DRAIN6_P$13") (pintype "bidirectional"))
      (node (ref "JP1") (pin "4") (pinfunction "4_4") (pintype "passive"))
      (node (ref "LED2") (pin "P$14") (pinfunction "14_P$14") (pintype "bidirectional"))
    )
    (net (code "111") (name "Net-(IC2-DRAIN7)") (class "Default")
      (node (ref "IC2") (pin "P$14") (pinfunction "DRAIN7_P$14") (pintype "bidirectional"))
      (node (ref "JP1") (pin "3") (pinfunction "3_3") (pintype "passive"))
      (node (ref "LED2") (pin "P$13") (pinfunction "13_P$13") (pintype "bidirectional"))
    )
    (net (code "112") (name "Net-(IC2-DRAIN8)") (class "Default")
      (node (ref "IC2") (pin "P$15") (pinfunction "DRAIN8_P$15") (pintype "bidirectional"))
      (node (ref "JP1") (pin "2") (pinfunction "2_2") (pintype "passive"))
      (node (ref "LED2") (pin "P$12") (pinfunction "12_P$12") (pintype "bidirectional"))
    )
    (net (code "113") (name "Net-(IC2-DRAIN9)") (class "Default")
      (node (ref "IC2") (pin "P$16") (pinfunction "DRAIN9_P$16") (pintype "bidirectional"))
      (node (ref "JP1") (pin "1") (pinfunction "1_1") (pintype "passive"))
      (node (ref "LED2") (pin "P$11") (pinfunction "11_P$11") (pintype "bidirectional"))
    )
    (net (code "114") (name "Net-(IRLS3034-7P-DRAIN)") (class "Default")
      (node (ref "C14") (pin "1") (pinfunction "1_1") (pintype "passive"))
      (node (ref "IRLS3034-7P") (pin "PAD") (pinfunction "DRAIN_PAD") (pintype "bidirectional"))
      (node (ref "IRLS3034-7P.2") (pin "PAD") (pinfunction "DRAIN_PAD") (pintype "bidirectional"))
      (node (ref "R41") (pin "2") (pinfunction "2_2") (pintype "passive"))
      (node (ref "S1") (pin "1") (pinfunction "O_1") (pintype "passive"))
      (node (ref "U$2") (pin "5_1") (pinfunction "IP-_5_1") (pintype "bidirectional"))
      (node (ref "U$2") (pin "5_10") (pinfunction "IP-_5_10") (pintype "bidirectional"))
      (node (ref "U$2") (pin "5_11") (pinfunction "IP-_5_11") (pintype "bidirectional"))
      (node (ref "U$2") (pin "5_12") (pinfunction "IP-_5_12") (pintype "bidirectional"))
      (node (ref "U$2") (pin "5_13") (pinfunction "IP-_5_13") (pintype "bidirectional"))
      (node (ref "U$2") (pin "5_14") (pinfunction "IP-_5_14") (pintype "bidirectional"))
      (node (ref "U$2") (pin "5_15") (pinfunction "IP-_5_15") (pintype "bidirectional"))
      (node (ref "U$2") (pin "5_16") (pinfunction "IP-_5_16") (pintype "bidirectional"))
      (node (ref "U$2") (pin "5_2") (pinfunction "IP-_5_2") (pintype "bidirectional"))
      (node (ref "U$2") (pin "5_3") (pinfunction "IP-_5_3") (pintype "bidirectional"))
      (node (ref "U$2") (pin "5_4") (pinfunction "IP-_5_4") (pintype "bidirectional"))
      (node (ref "U$2") (pin "5_5") (pinfunction "IP-_5_5") (pintype "bidirectional"))
      (node (ref "U$2") (pin "5_6") (pinfunction "IP-_5_6") (pintype "bidirectional"))
      (node (ref "U$2") (pin "5_7") (pinfunction "IP-_5_7") (pintype "bidirectional"))
      (node (ref "U$2") (pin "5_8") (pinfunction "IP-_5_8") (pintype "bidirectional"))
      (node (ref "U$2") (pin "5_9") (pinfunction "IP-_5_9") (pintype "bidirectional"))
      (node (ref "U$2") (pin "5_B") (pinfunction "IP-_5_B") (pintype "bidirectional"))
      (node (ref "U$2") (pin "5_T") (pinfunction "IP-_5_T") (pintype "bidirectional"))
      (node (ref "U$4") (pin "4_1") (pinfunction "IP+_4_1") (pintype "bidirectional"))
      (node (ref "U$4") (pin "4_10") (pinfunction "IP+_4_10") (pintype "bidirectional"))
      (node (ref "U$4") (pin "4_11") (pinfunction "IP+_4_11") (pintype "bidirectional"))
      (node (ref "U$4") (pin "4_12") (pinfunction "IP+_4_12") (pintype "bidirectional"))
      (node (ref "U$4") (pin "4_13") (pinfunction "IP+_4_13") (pintype "bidirectional"))
      (node (ref "U$4") (pin "4_14") (pinfunction "IP+_4_14") (pintype "bidirectional"))
      (node (ref "U$4") (pin "4_15") (pinfunction "IP+_4_15") (pintype "bidirectional"))
      (node (ref "U$4") (pin "4_16") (pinfunction "IP+_4_16") (pintype "bidirectional"))
      (node (ref "U$4") (pin "4_2") (pinfunction "IP+_4_2") (pintype "bidirectional"))
      (node (ref "U$4") (pin "4_3") (pinfunction "IP+_4_3") (pintype "bidirectional"))
      (node (ref "U$4") (pin "4_4") (pinfunction "IP+_4_4") (pintype "bidirectional"))
      (node (ref "U$4") (pin "4_5") (pinfunction "IP+_4_5") (pintype "bidirectional"))
      (node (ref "U$4") (pin "4_6") (pinfunction "IP+_4_6") (pintype "bidirectional"))
      (node (ref "U$4") (pin "4_7") (pinfunction "IP+_4_7") (pintype "bidirectional"))
      (node (ref "U$4") (pin "4_8") (pinfunction "IP+_4_8") (pintype "bidirectional"))
      (node (ref "U$4") (pin "4_9") (pinfunction "IP+_4_9") (pintype "bidirectional"))
      (node (ref "U$4") (pin "4_B") (pinfunction "IP+_4_B") (pintype "bidirectional"))
      (node (ref "U$4") (pin "4_T") (pinfunction "IP+_4_T") (pintype "bidirectional"))
      (node (ref "U$8") (pin "6") (pinfunction "SENSE_6") (pintype "bidirectional"))
      (node (ref "U$8") (pin "8") (pinfunction "V+_8") (pintype "bidirectional"))
    )
    (net (code "115") (name "Net-(IRLS3034-7P-GATE)") (class "Default")
      (node (ref "IRLS3034-7P") (pin "1") (pinfunction "GATE_1") (pintype "bidirectional"))
      (node (ref "IRLS3034-7P.2") (pin "1") (pinfunction "GATE_1") (pintype "bidirectional"))
      (node (ref "U$8") (pin "5") (pinfunction "GATE_5") (pintype "bidirectional"))
    )
    (net (code "116") (name "Net-(IRLS3034-7P-SOURCE-Pad2)") (class "Default")
      (node (ref "IRLS3034-7P") (pin "2") (pinfunction "SOURCE_2") (pintype "bidirectional"))
      (node (ref "IRLS3034-7P") (pin "3") (pinfunction "SOURCE_3") (pintype "bidirectional"))
      (node (ref "IRLS3034-7P") (pin "4") (pinfunction "SOURCE_4") (pintype "bidirectional"))
      (node (ref "IRLS3034-7P") (pin "5") (pinfunction "SOURCE_5") (pintype "bidirectional"))
      (node (ref "IRLS3034-7P") (pin "6") (pinfunction "SOURCE_6") (pintype "bidirectional"))
      (node (ref "IRLS3034-7P.2") (pin "2") (pinfunction "SOURCE_2") (pintype "bidirectional"))
      (node (ref "IRLS3034-7P.2") (pin "3") (pinfunction "SOURCE_3") (pintype "bidirectional"))
      (node (ref "IRLS3034-7P.2") (pin "4") (pinfunction "SOURCE_4") (pintype "bidirectional"))
      (node (ref "IRLS3034-7P.2") (pin "5") (pinfunction "SOURCE_5") (pintype "bidirectional"))
      (node (ref "IRLS3034-7P.2") (pin "6") (pinfunction "SOURCE_6") (pintype "bidirectional"))
      (node (ref "LED1") (pin "A") (pinfunction "A_A") (pintype "passive"))
      (node (ref "R38") (pin "1") (pinfunction "1_1") (pintype "passive"))
      (node (ref "V_OUT") (pin "P$1") (pinfunction "P$1_P$1") (pintype "bidirectional"))
    )
    (net (code "117") (name "Net-(LED1-PadC)") (class "Default")
      (node (ref "LED1") (pin "C") (pinfunction "C_C") (pintype "passive"))
      (node (ref "R40") (pin "1") (pinfunction "1_1") (pintype "passive"))
    )
    (net (code "118") (name "Net-(LED2-1)") (class "Default")
      (node (ref "LED2") (pin "P$1") (pinfunction "1_P$1") (pintype "bidirectional"))
      (node (ref "R47") (pin "1") (pinfunction "1_1") (pintype "passive"))
    )
    (net (code "119") (name "Net-(LED2-2)") (class "Default")
      (node (ref "LED2") (pin "P$2") (pinfunction "2_P$2") (pintype "bidirectional"))
      (node (ref "R48") (pin "1") (pinfunction "1_1") (pintype "passive"))
    )
    (net (code "120") (name "Net-(LED2-3)") (class "Default")
      (node (ref "LED2") (pin "P$3") (pinfunction "3_P$3") (pintype "bidirectional"))
      (node (ref "R49") (pin "1") (pinfunction "1_1") (pintype "passive"))
    )
    (net (code "121") (name "Net-(LED2-4)") (class "Default")
      (node (ref "LED2") (pin "P$4") (pinfunction "4_P$4") (pintype "bidirectional"))
      (node (ref "R50") (pin "1") (pinfunction "1_1") (pintype "passive"))
    )
    (net (code "122") (name "Net-(LED2-5)") (class "Default")
      (node (ref "LED2") (pin "P$5") (pinfunction "5_P$5") (pintype "bidirectional"))
      (node (ref "R51") (pin "1") (pinfunction "1_1") (pintype "passive"))
    )
    (net (code "123") (name "Net-(LED2-6)") (class "Default")
      (node (ref "LED2") (pin "P$6") (pinfunction "6_P$6") (pintype "bidirectional"))
      (node (ref "R52") (pin "1") (pinfunction "1_1") (pintype "passive"))
    )
    (net (code "124") (name "Net-(LED2-7)") (class "Default")
      (node (ref "LED2") (pin "P$7") (pinfunction "7_P$7") (pintype "bidirectional"))
      (node (ref "R53") (pin "1") (pinfunction "1_1") (pintype "passive"))
    )
    (net (code "125") (name "Net-(LED2-8)") (class "Default")
      (node (ref "LED2") (pin "P$8") (pinfunction "8_P$8") (pintype "bidirectional"))
      (node (ref "R54") (pin "1") (pinfunction "1_1") (pintype "passive"))
    )
    (net (code "126") (name "Net-(LED2-9)") (class "Default")
      (node (ref "LED2") (pin "P$9") (pinfunction "9_P$9") (pintype "bidirectional"))
      (node (ref "R55") (pin "1") (pinfunction "1_1") (pintype "passive"))
    )
    (net (code "127") (name "Net-(LED2-10)") (class "Default")
      (node (ref "LED2") (pin "P$10") (pinfunction "10_P$10") (pintype "bidirectional"))
      (node (ref "R56") (pin "1") (pinfunction "1_1") (pintype "passive"))
    )
    (net (code "128") (name "Net-(OKI-78SR-VO)") (class "Default")
      (node (ref "C17") (pin "1") (pinfunction "1_1") (pintype "passive"))
      (node (ref "L3") (pin "1") (pinfunction "1_1") (pintype "passive"))
      (node (ref "OKI-78SR") (pin "3") (pinfunction "VO_3") (pintype "bidirectional"))
    )
    (net (code "129") (name "Net-(OKI-78SR1-VO)") (class "Default")
      (node (ref "C19") (pin "1") (pinfunction "1_1") (pintype "passive"))
      (node (ref "L2") (pin "1") (pinfunction "1_1") (pintype "passive"))
      (node (ref "OKI-78SR1") (pin "3") (pinfunction "VO_3") (pintype "bidirectional"))
    )
    (net (code "130") (name "Net-(Q1-D)") (class "Default")
      (node (ref "Q1") (pin "3") (pinfunction "D_3") (pintype "passive"))
      (node (ref "R2") (pin "P$1") (pinfunction "1_P$1") (pintype "passive"))
      (node (ref "R3") (pin "1") (pinfunction "1_1") (pintype "passive"))
    )
    (net (code "131") (name "Net-(Q1-G)") (class "Default")
      (node (ref "Q1") (pin "1") (pinfunction "G_1") (pintype "passive"))
      (node (ref "R4") (pin "2") (pinfunction "2_2") (pintype "passive"))
    )
    (net (code "132") (name "Net-(Q2-D)") (class "Default")
      (node (ref "Q2") (pin "3") (pinfunction "D_3") (pintype "passive"))
      (node (ref "R6") (pin "P$1") (pinfunction "1_P$1") (pintype "passive"))
      (node (ref "R7") (pin "1") (pinfunction "1_1") (pintype "passive"))
    )
    (net (code "133") (name "Net-(Q2-G)") (class "Default")
      (node (ref "Q2") (pin "1") (pinfunction "G_1") (pintype "passive"))
      (node (ref "R8") (pin "2") (pinfunction "2_2") (pintype "passive"))
    )
    (net (code "134") (name "Net-(Q3-D)") (class "Default")
      (node (ref "Q3") (pin "3") (pinfunction "D_3") (pintype "passive"))
      (node (ref "R10") (pin "P$1") (pinfunction "1_P$1") (pintype "passive"))
      (node (ref "R11") (pin "1") (pinfunction "1_1") (pintype "passive"))
    )
    (net (code "135") (name "Net-(Q3-G)") (class "Default")
      (node (ref "Q3") (pin "1") (pinfunction "G_1") (pintype "passive"))
      (node (ref "R12") (pin "2") (pinfunction "2_2") (pintype "passive"))
    )
    (net (code "136") (name "Net-(Q4-D)") (class "Default")
      (node (ref "Q4") (pin "3") (pinfunction "D_3") (pintype "passive"))
      (node (ref "R14") (pin "P$1") (pinfunction "1_P$1") (pintype "passive"))
      (node (ref "R15") (pin "1") (pinfunction "1_1") (pintype "passive"))
    )
    (net (code "137") (name "Net-(Q4-G)") (class "Default")
      (node (ref "Q4") (pin "1") (pinfunction "G_1") (pintype "passive"))
      (node (ref "R16") (pin "2") (pinfunction "2_2") (pintype "passive"))
    )
    (net (code "138") (name "Net-(Q5-D)") (class "Default")
      (node (ref "Q5") (pin "3") (pinfunction "D_3") (pintype "passive"))
      (node (ref "R18") (pin "P$1") (pinfunction "1_P$1") (pintype "passive"))
      (node (ref "R19") (pin "1") (pinfunction "1_1") (pintype "passive"))
    )
    (net (code "139") (name "Net-(Q5-G)") (class "Default")
      (node (ref "Q5") (pin "1") (pinfunction "G_1") (pintype "passive"))
      (node (ref "R20") (pin "2") (pinfunction "2_2") (pintype "passive"))
    )
    (net (code "140") (name "Net-(Q6-D)") (class "Default")
      (node (ref "Q6") (pin "3") (pinfunction "D_3") (pintype "passive"))
      (node (ref "R22") (pin "P$1") (pinfunction "1_P$1") (pintype "passive"))
      (node (ref "R23") (pin "1") (pinfunction "1_1") (pintype "passive"))
    )
    (net (code "141") (name "Net-(Q6-G)") (class "Default")
      (node (ref "Q6") (pin "1") (pinfunction "G_1") (pintype "passive"))
      (node (ref "R24") (pin "2") (pinfunction "2_2") (pintype "passive"))
    )
    (net (code "142") (name "Net-(Q7-D)") (class "Default")
      (node (ref "Q7") (pin "3") (pinfunction "D_3") (pintype "passive"))
      (node (ref "R26") (pin "P$1") (pinfunction "1_P$1") (pintype "passive"))
      (node (ref "R27") (pin "1") (pinfunction "1_1") (pintype "passive"))
    )
    (net (code "143") (name "Net-(Q7-G)") (class "Default")
      (node (ref "Q7") (pin "1") (pinfunction "G_1") (pintype "passive"))
      (node (ref "R28") (pin "2") (pinfunction "2_2") (pintype "passive"))
    )
    (net (code "144") (name "Net-(Q8-D)") (class "Default")
      (node (ref "Q8") (pin "3") (pinfunction "D_3") (pintype "passive"))
      (node (ref "R30") (pin "P$1") (pinfunction "1_P$1") (pintype "passive"))
      (node (ref "R31") (pin "1") (pinfunction "1_1") (pintype "passive"))
    )
    (net (code "145") (name "Net-(Q8-G)") (class "Default")
      (node (ref "Q8") (pin "1") (pinfunction "G_1") (pintype "passive"))
      (node (ref "R32") (pin "2") (pinfunction "2_2") (pintype "passive"))
    )
    (net (code "146") (name "Net-(Q9-G)") (class "Default")
      (node (ref "Q9") (pin "1") (pinfunction "G_1") (pintype "bidirectional"))
      (node (ref "U$12") (pin "P$7") (pinfunction "TG_P$7") (pintype "bidirectional"))
    )
    (net (code "147") (name "Net-(Q9-S)") (class "Default")
      (node (ref "C15") (pin "2") (pinfunction "2_2") (pintype "passive"))
      (node (ref "Q9") (pin "3") (pinfunction "S_3") (pintype "bidirectional"))
      (node (ref "U$12") (pin "P$8") (pinfunction "TS_P$8") (pintype "bidirectional"))
      (node (ref "U$5") (pin "P$2") (pinfunction "2_P$2") (pintype "passive"))
      (node (ref "U$9") (pin "P$2") (pinfunction "C_P$2") (pintype "passive"))
    )
    (net (code "148") (name "Net-(Q12-D)") (class "Default")
      (node (ref "Q12") (pin "3") (pinfunction "D_3") (pintype "passive"))
      (node (ref "X1") (pin "1") (pinfunction "S_1") (pintype "passive"))
    )
    (net (code "149") (name "Net-(Q13-D)") (class "Default")
      (node (ref "Q13") (pin "3") (pinfunction "D_3") (pintype "passive"))
      (node (ref "X2") (pin "1") (pinfunction "S_1") (pintype "passive"))
    )
    (net (code "150") (name "Net-(Q14-D)") (class "Default")
      (node (ref "Q14") (pin "3") (pinfunction "D_3") (pintype "passive"))
      (node (ref "X3") (pin "1") (pinfunction "S_1") (pintype "passive"))
    )
    (net (code "151") (name "Net-(Q15-D)") (class "Default")
      (node (ref "Q15") (pin "3") (pinfunction "D_3") (pintype "passive"))
      (node (ref "X4") (pin "1") (pinfunction "S_1") (pintype "passive"))
    )
    (net (code "152") (name "Net-(R72-Pad1)") (class "Default")
      (node (ref "R72") (pin "1") (pinfunction "1_1") (pintype "passive"))
      (node (ref "U$14") (pin "3") (pinfunction "3_3") (pintype "bidirectional"))
      (node (ref "U$15") (pin "A") (pinfunction "A_A") (pintype "bidirectional"))
    )
    (net (code "153") (name "Net-(R72-Pad2)") (class "Default")
      (node (ref "R72") (pin "2") (pinfunction "2_2") (pintype "passive"))
      (node (ref "U$14") (pin "6") (pinfunction "6_6") (pintype "bidirectional"))
      (node (ref "U$15") (pin "B") (pinfunction "B_B") (pintype "bidirectional"))
    )
    (net (code "154") (name "Net-(R73-Pad1)") (class "Default")
      (node (ref "R73") (pin "1") (pinfunction "1_1") (pintype "passive"))
      (node (ref "U$14") (pin "2") (pinfunction "2_2") (pintype "bidirectional"))
      (node (ref "U$15") (pin "Z") (pinfunction "Z_Z") (pintype "bidirectional"))
    )
    (net (code "155") (name "Net-(R73-Pad2)") (class "Default")
      (node (ref "R73") (pin "2") (pinfunction "2_2") (pintype "passive"))
      (node (ref "U$14") (pin "1") (pinfunction "1_1") (pintype "bidirectional"))
      (node (ref "U$15") (pin "Y") (pinfunction "Y_Y") (pintype "bidirectional"))
    )
    (net (code "156") (name "Net-(S1-P)") (class "Default")
      (node (ref "F1") (pin "1") (pinfunction "1_1") (pintype "bidirectional"))
      (node (ref "S1") (pin "2") (pinfunction "P_2") (pintype "passive"))
    )
    (net (code "157") (name "Net-(THERM_1A-S)") (class "Default")
      (node (ref "R33") (pin "2") (pinfunction "2_2") (pintype "passive"))
      (node (ref "R34") (pin "2") (pinfunction "2_2") (pintype "passive"))
      (node (ref "THERM_1") (pin "1") (pinfunction "S_1") (pintype "passive"))
    )
    (net (code "158") (name "Net-(THERM_2A-S)") (class "Default")
      (node (ref "R35") (pin "2") (pinfunction "2_2") (pintype "passive"))
      (node (ref "R36") (pin "2") (pinfunction "2_2") (pintype "passive"))
      (node (ref "THERM_2") (pin "1") (pinfunction "S_1") (pintype "passive"))
    )
    (net (code "159") (name "Net-(U$1-S1)") (class "Default")
      (node (ref "R4") (pin "1") (pinfunction "1_1") (pintype "passive"))
      (node (ref "U$1") (pin "25") (pinfunction "S1_25") (pintype "bidirectional"))
    )
    (net (code "160") (name "Net-(U$1-V+)") (class "Default")
      (node (ref "C13") (pin "1") (pinfunction "1_1") (pintype "passive"))
      (node (ref "R37") (pin "1") (pinfunction "1_1") (pintype "passive"))
      (node (ref "U$1") (pin "1") (pinfunction "V+_1") (pintype "bidirectional"))
    )
    (net (code "161") (name "Net-(U$5-1)") (class "Default")
      (node (ref "U$3") (pin "+") (pinfunction "+_+") (pintype "passive"))
      (node (ref "U$4") (pin "5_1") (pinfunction "IP-_5_1") (pintype "bidirectional"))
      (node (ref "U$4") (pin "5_10") (pinfunction "IP-_5_10") (pintype "bidirectional"))
      (node (ref "U$4") (pin "5_11") (pinfunction "IP-_5_11") (pintype "bidirectional"))
      (node (ref "U$4") (pin "5_12") (pinfunction "IP-_5_12") (pintype "bidirectional"))
      (node (ref "U$4") (pin "5_13") (pinfunction "IP-_5_13") (pintype "bidirectional"))
      (node (ref "U$4") (pin "5_14") (pinfunction "IP-_5_14") (pintype "bidirectional"))
      (node (ref "U$4") (pin "5_15") (pinfunction "IP-_5_15") (pintype "bidirectional"))
      (node (ref "U$4") (pin "5_16") (pinfunction "IP-_5_16") (pintype "bidirectional"))
      (node (ref "U$4") (pin "5_2") (pinfunction "IP-_5_2") (pintype "bidirectional"))
      (node (ref "U$4") (pin "5_3") (pinfunction "IP-_5_3") (pintype "bidirectional"))
      (node (ref "U$4") (pin "5_4") (pinfunction "IP-_5_4") (pintype "bidirectional"))
      (node (ref "U$4") (pin "5_5") (pinfunction "IP-_5_5") (pintype "bidirectional"))
      (node (ref "U$4") (pin "5_6") (pinfunction "IP-_5_6") (pintype "bidirectional"))
      (node (ref "U$4") (pin "5_7") (pinfunction "IP-_5_7") (pintype "bidirectional"))
      (node (ref "U$4") (pin "5_8") (pinfunction "IP-_5_8") (pintype "bidirectional"))
      (node (ref "U$4") (pin "5_9") (pinfunction "IP-_5_9") (pintype "bidirectional"))
      (node (ref "U$4") (pin "5_B") (pinfunction "IP-_5_B") (pintype "bidirectional"))
      (node (ref "U$4") (pin "5_T") (pinfunction "IP-_5_T") (pintype "bidirectional"))
      (node (ref "U$5") (pin "P$1") (pinfunction "1_P$1") (pintype "passive"))
      (node (ref "U$6") (pin "+") (pinfunction "+_+") (pintype "passive"))
      (node (ref "U$7") (pin "+") (pinfunction "+_+") (pintype "passive"))
    )
    (net (code "162") (name "unconnected-(IC2-DRAIN10-PadP$17)") (class "Default")
      (node (ref "IC2") (pin "P$17") (pinfunction "DRAIN10_P$17") (pintype "bidirectional"))
    )
    (net (code "163") (name "unconnected-(IC2-DRAIN11-PadP$18)") (class "Default")
      (node (ref "IC2") (pin "P$18") (pinfunction "DRAIN11_P$18") (pintype "bidirectional"))
    )
    (net (code "164") (name "unconnected-(IC2-SER_OUT-PadP$11)") (class "Default")
      (node (ref "IC2") (pin "P$11") (pinfunction "SER_OUT_P$11") (pintype "bidirectional"))
    )
    (net (code "165") (name "unconnected-(U$1-MMB-Pad33)") (class "Default")
      (node (ref "U$1") (pin "33") (pinfunction "MMB_33") (pintype "bidirectional"))
    )
    (net (code "166") (name "unconnected-(U$1-NC-Pad27)") (class "Default")
      (node (ref "U$1") (pin "27") (pinfunction "NC_27") (pintype "bidirectional"))
    )
    (net (code "167") (name "unconnected-(U$1-S9-Pad9)") (class "Default")
      (node (ref "U$1") (pin "9") (pinfunction "S9_9") (pintype "bidirectional"))
    )
    (net (code "168") (name "unconnected-(U$1-S10-Pad7)") (class "Default")
      (node (ref "U$1") (pin "7") (pinfunction "S10_7") (pintype "bidirectional"))
    )
    (net (code "169") (name "unconnected-(U$1-S11-Pad5)") (class "Default")
      (node (ref "U$1") (pin "5") (pinfunction "S11_5") (pintype "bidirectional"))
    )
    (net (code "170") (name "unconnected-(U$1-S12-Pad3)") (class "Default")
      (node (ref "U$1") (pin "3") (pinfunction "S12_3") (pintype "bidirectional"))
    )
    (net (code "171") (name "unconnected-(U$1-WDTB-Pad34)") (class "Default")
      (node (ref "U$1") (pin "34") (pinfunction "WDTB_34") (pintype "bidirectional"))
    )
    (net (code "172") (name "unconnected-(U$8-FAULT-Pad3)") (class "Default")
      (node (ref "U$8") (pin "3") (pinfunction "FAULT_3") (pintype "bidirectional"))
    )
    (net (code "173") (name "unconnected-(U$8-TIMER-Pad2)") (class "Default")
      (node (ref "U$8") (pin "2") (pinfunction "TIMER_2") (pintype "bidirectional"))
    )
    (net (code "174") (name "unconnected-(U$13-P6.1-Pad6.1)") (class "Default")
      (node (ref "U$13") (pin "6.1") (pinfunction "P6.1_6.1") (pintype "bidirectional"))
    )
    (net (code "175") (name "unconnected-(U$13-P6.7-Pad6.7)") (class "Default")
      (node (ref "U$13") (pin "6.7") (pinfunction "P6.7_6.7") (pintype "bidirectional"))
    )
    (net (code "176") (name "unconnected-(U$13-P7.0-Pad7.0)") (class "Default")
      (node (ref "U$13") (pin "7.0") (pinfunction "P7.0_7.0") (pintype "bidirectional"))
    )
    (net (code "177") (name "unconnected-(U$13-P7.1-Pad7.1)") (class "Default")
      (node (ref "U$13") (pin "7.1") (pinfunction "P7.1_7.1") (pintype "bidirectional"))
    )
    (net (code "178") (name "unconnected-(U$13-P7.2-Pad7.2)") (class "Default")
      (node (ref "U$13") (pin "7.2") (pinfunction "P7.2_7.2") (pintype "bidirectional"))
    )
    (net (code "179") (name "unconnected-(U$13-P7.3-Pad7.3)") (class "Default")
      (node (ref "U$13") (pin "7.3") (pinfunction "P7.3_7.3") (pintype "bidirectional"))
    )
    (net (code "180") (name "unconnected-(U$13-P7.4-Pad7.4)") (class "Default")
      (node (ref "U$13") (pin "7.4") (pinfunction "P7.4_7.4") (pintype "bidirectional"))
    )
    (net (code "181") (name "unconnected-(U$13-P7.5-Pad7.5)") (class "Default")
      (node (ref "U$13") (pin "7.5") (pinfunction "P7.5_7.5") (pintype "bidirectional"))
    )
    (net (code "182") (name "unconnected-(U$13-P7.6-Pad7.6)") (class "Default")
      (node (ref "U$13") (pin "7.6") (pinfunction "P7.6_7.6") (pintype "bidirectional"))
    )
    (net (code "183") (name "unconnected-(U$13-P7.7-Pad7.7)") (class "Default")
      (node (ref "U$13") (pin "7.7") (pinfunction "P7.7_7.7") (pintype "bidirectional"))
    )
    (net (code "184") (name "unconnected-(U$13-P8.2-Pad8.2)") (class "Default")
      (node (ref "U$13") (pin "8.2") (pinfunction "P8.2_8.2") (pintype "bidirectional"))
    )
    (net (code "185") (name "unconnected-(U$13-P8.3-Pad8.3)") (class "Default")
      (node (ref "U$13") (pin "8.3") (pinfunction "P8.3_8.3") (pintype "bidirectional"))
    )
    (net (code "186") (name "unconnected-(U$13-P8.4-Pad8.4)") (class "Default")
      (node (ref "U$13") (pin "8.4") (pinfunction "P8.4_8.4") (pintype "bidirectional"))
    )
    (net (code "187") (name "unconnected-(U$13-P8.5-Pad8.5)") (class "Default")
      (node (ref "U$13") (pin "8.5") (pinfunction "P8.5_8.5") (pintype "bidirectional"))
    )
    (net (code "188") (name "unconnected-(U$13-P8.6-Pad8.6)") (class "Default")
      (node (ref "U$13") (pin "8.6") (pinfunction "P8.6_8.6") (pintype "bidirectional"))
    )
    (net (code "189") (name "unconnected-(U$13-P8.7-Pad8.7)") (class "Default")
      (node (ref "U$13") (pin "8.7") (pinfunction "P8.7_8.7") (pintype "bidirectional"))
    )
    (net (code "190") (name "unconnected-(U$13-P9.0-Pad9.0)") (class "Default")
      (node (ref "U$13") (pin "9.0") (pinfunction "P9.0_9.0") (pintype "bidirectional"))
    )
    (net (code "191") (name "unconnected-(U$13-P9.1-Pad9.1)") (class "Default")
      (node (ref "U$13") (pin "9.1") (pinfunction "P9.1_9.1") (pintype "bidirectional"))
    )
    (net (code "192") (name "unconnected-(U$13-P9.2-Pad9.2)") (class "Default")
      (node (ref "U$13") (pin "9.2") (pinfunction "P9.2_9.2") (pintype "bidirectional"))
    )
    (net (code "193") (name "unconnected-(U$13-P9.3-Pad9.3)") (class "Default")
      (node (ref "U$13") (pin "9.3") (pinfunction "P9.3_9.3") (pintype "bidirectional"))
    )
    (net (code "194") (name "unconnected-(U$13-P9.4-Pad9.4)") (class "Default")
      (node (ref "U$13") (pin "9.4") (pinfunction "P9.4_9.4") (pintype "bidirectional"))
    )
    (net (code "195") (name "unconnected-(U$13-P9.5-Pad9.5)") (class "Default")
      (node (ref "U$13") (pin "9.5") (pinfunction "P9.5_9.5") (pintype "bidirectional"))
    )
    (net (code "196") (name "unconnected-(U$13-P10.4-Pad10.4)") (class "Default")
      (node (ref "U$13") (pin "10.4") (pinfunction "P10.4_10.4") (pintype "bidirectional"))
    )
    (net (code "197") (name "unconnected-(U$13-P10.5-Pad10.5)") (class "Default")
      (node (ref "U$13") (pin "10.5") (pinfunction "P10.5_10.5") (pintype "bidirectional"))
    )
    (net (code "198") (name "unconnected-(U$13-{slash}RST-PadRST)") (class "Default")
      (node (ref "U$13") (pin "RST") (pinfunction "/RST_RST") (pintype "bidirectional"))
    )
    (net (code "199") (name "unconnected-(U$14-Pad4)") (class "Default")
      (node (ref "U$14") (pin "4") (pinfunction "4_4") (pintype "bidirectional"))
    )
    (net (code "200") (name "unconnected-(U$14-Pad5)") (class "Default")
      (node (ref "U$14") (pin "5") (pinfunction "5_5") (pintype "bidirectional"))
    )
  )
)
